# panda-2.net
KiCad netlist of a schematic drawn in EAGLE
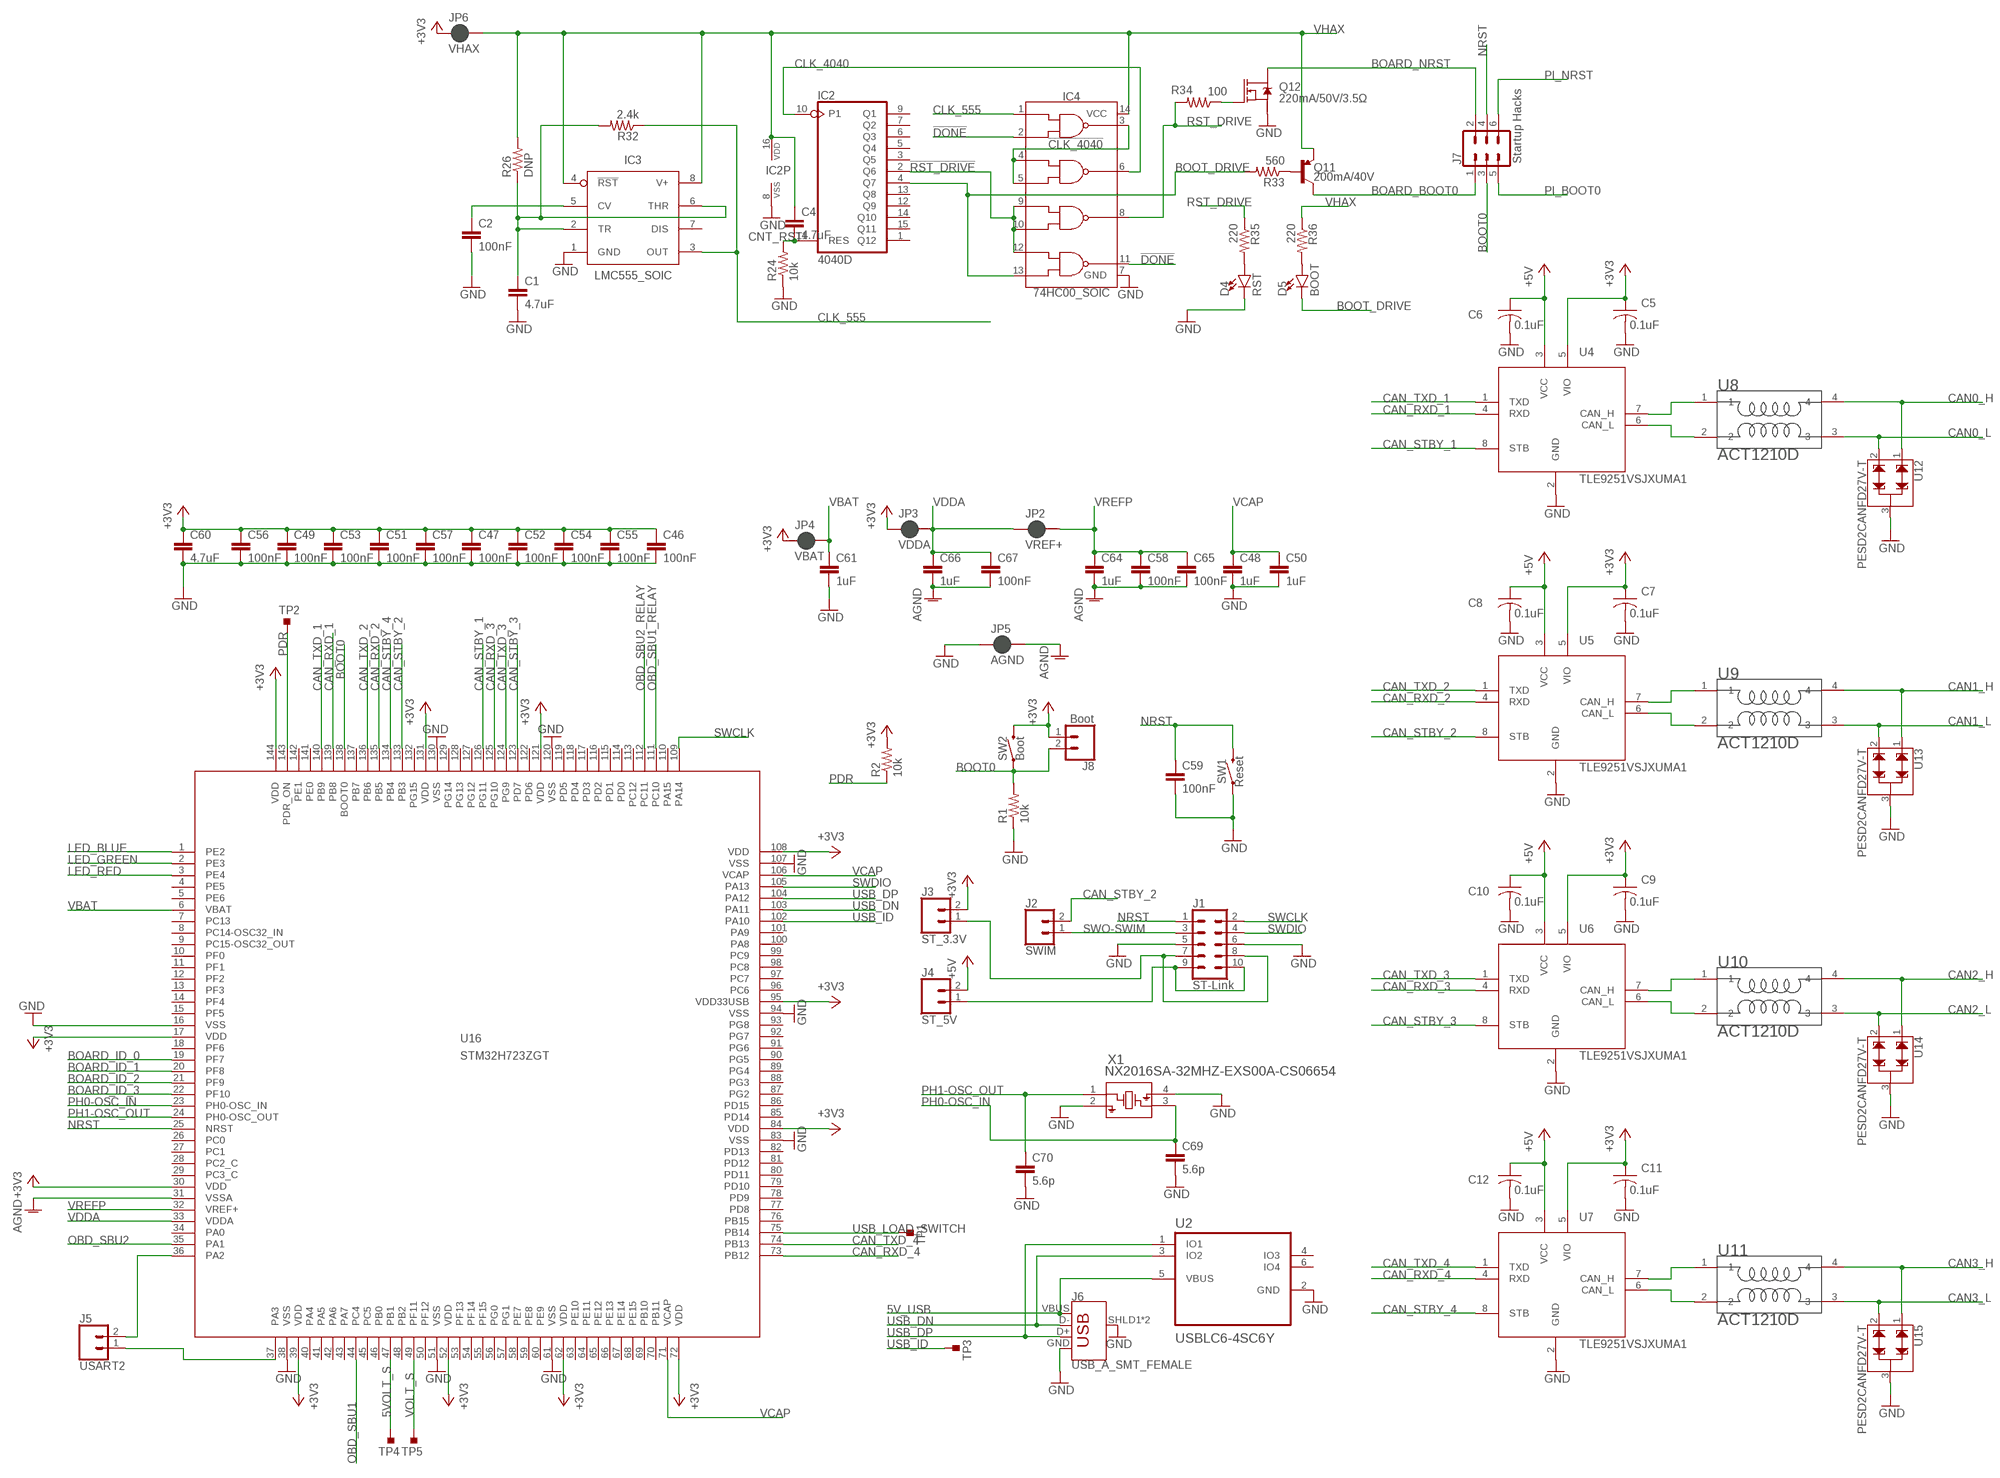
[diagram p0: schematic, sheet 1, part 1 of 2]
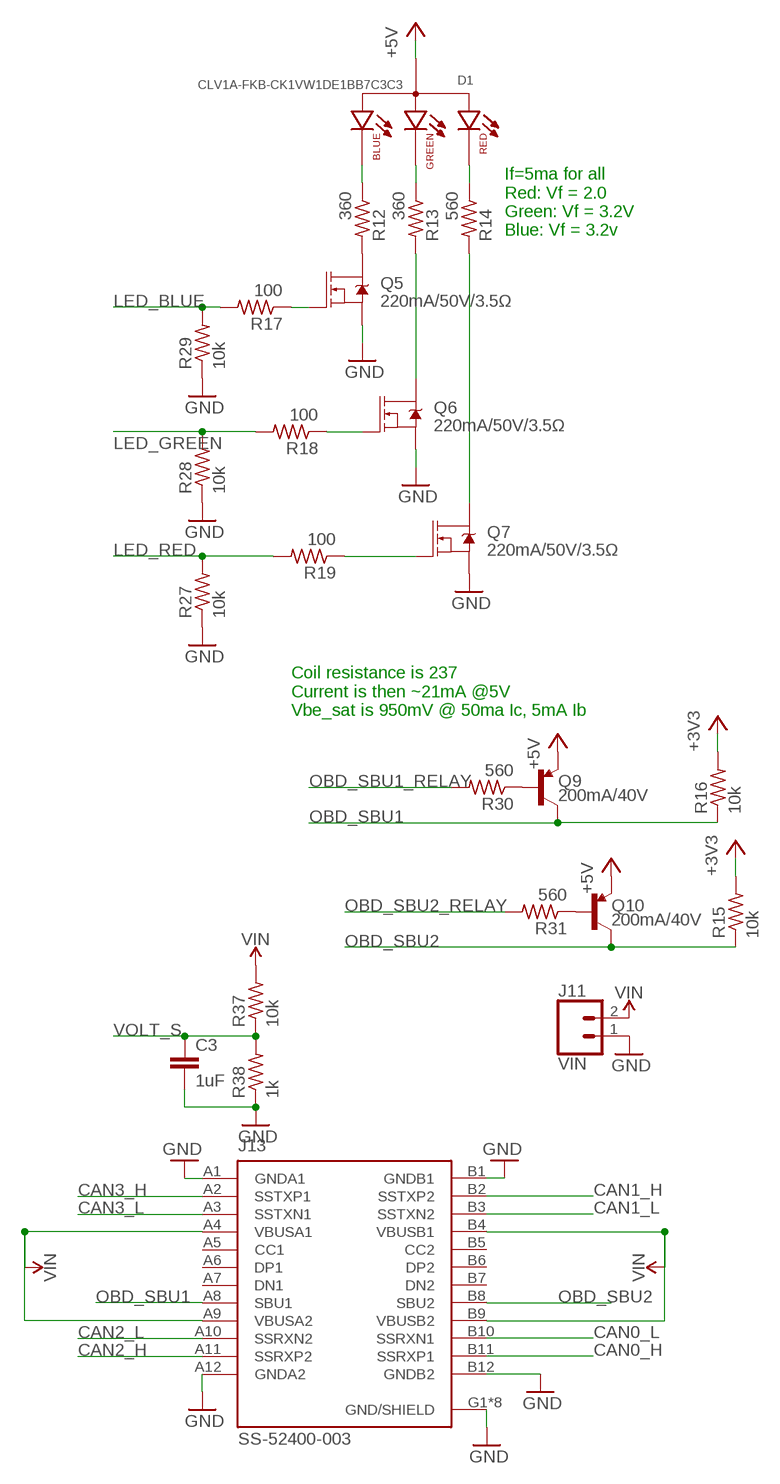
[diagram p1: schematic, sheet 1, part 2 of 2]
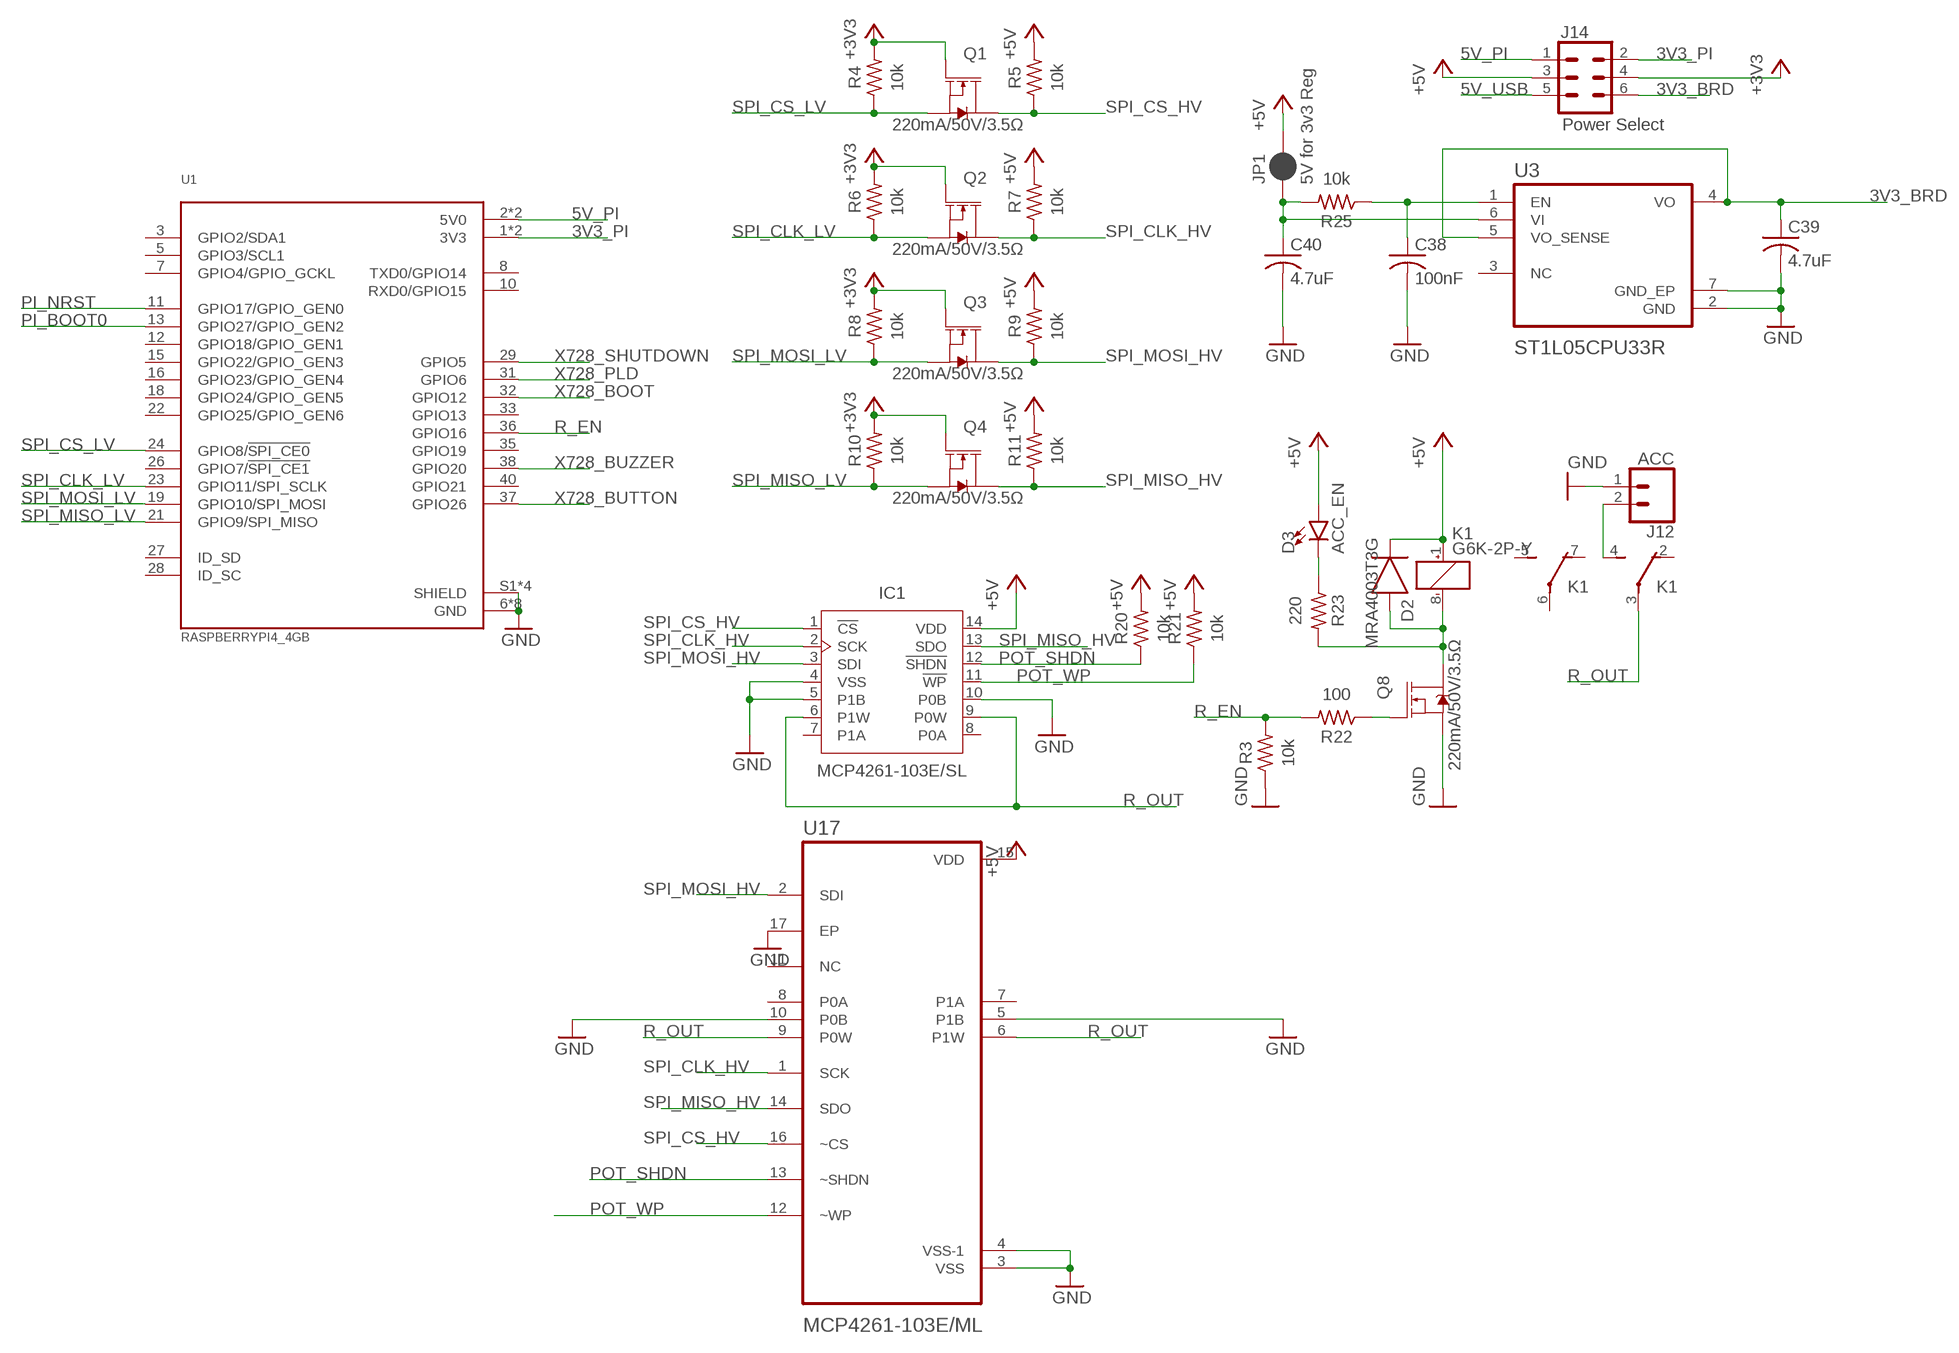
[diagram p2: schematic, sheet 2]

(export (version "E")
  (design (tool "Eeschema 10.0.6"))
  (components
    (comp (ref "C38")
      (value "100nF")
      (footprint "eagle-import:CAPC1005X60")
      (libsource (lib "eagle-import") (part "C-USCHIP-0402(1005-METRIC)_"))
    )
    (comp (ref "C39")
      (value "4.7uF")
      (footprint "eagle-import:CAPC1608X85")
      (libsource (lib "eagle-import") (part "C-USCHIP-0603(1608-METRIC)_"))
    )
    (comp (ref "C40")
      (value "4.7uF")
      (footprint "eagle-import:CAPC1608X85")
      (libsource (lib "eagle-import") (part "C-USCHIP-0603(1608-METRIC)_"))
    )
    (comp (ref "D2")
      (value "MRA4003T3G")
      (footprint "eagle-import:DIOM5226X290N")
      (fields (field (name "MANUFACTURER") "ON Semiconductor "))
      (libsource (lib "eagle-import") (part "DIODE__SMAMRA4003T3G"))
    )
    (comp (ref "D3")
      (value "ACC_EN")
      (footprint "eagle-import:LED-0603")
      (libsource (lib "eagle-import") (part "LED-RED0603"))
    )
    (comp (ref "IC1")
      (value "MCP4261-103E/SL")
      (footprint "eagle-import:SOIC127P600X175-14N")
      (fields (field (name "MANUFACTURER") "Microchip Technology"))
      (libsource (lib "eagle-import") (part "MCP42SOIC-1461-103E/SL"))
    )
    (comp (ref "J12")
      (value "ACC")
      (footprint "eagle-import:SCREWTERMINAL-5MM-2")
      (libsource (lib "eagle-import") (part "CONN_025MM"))
    )
    (comp (ref "J14")
      (value "Power Select")
      (footprint "eagle-import:2X3")
      (libsource (lib "eagle-import") (part "CONN_03X2FEMALE"))
    )
    (comp (ref "JP1")
      (value "5V for 3v3 Reg")
      (footprint "eagle-import:SMT-JUMPER_2_NC_PASTE_SILK")
      (libsource (lib "eagle-import") (part "JUMPER-SMT_2_NC_PASTE_SILK"))
    )
    (comp (ref "K1")
      (value "G6K-2P-Y")
      (footprint "eagle-import:G6K-2P-Y")
      (fields (field (name "MF") "OMRON COMPONENTS USA") (field (name "MPN") "G6K-2P-Y DC12"))
      (libsource (lib "eagle-import") (part "G6K-2P-Y"))
    )
    (comp (ref "Q1")
      (value "220mA/50V/3.5Ω")
      (footprint "eagle-import:SOT23-3")
      (libsource (lib "eagle-import") (part "MOSFET-NCH-BSS138"))
    )
    (comp (ref "Q2")
      (value "220mA/50V/3.5Ω")
      (footprint "eagle-import:SOT23-3")
      (libsource (lib "eagle-import") (part "MOSFET-NCH-BSS138"))
    )
    (comp (ref "Q3")
      (value "220mA/50V/3.5Ω")
      (footprint "eagle-import:SOT23-3")
      (libsource (lib "eagle-import") (part "MOSFET-NCH-BSS138"))
    )
    (comp (ref "Q4")
      (value "220mA/50V/3.5Ω")
      (footprint "eagle-import:SOT23-3")
      (libsource (lib "eagle-import") (part "MOSFET-NCH-BSS138"))
    )
    (comp (ref "Q8")
      (value "220mA/50V/3.5Ω")
      (footprint "eagle-import:SOT23-3")
      (libsource (lib "eagle-import") (part "MOSFET-NCH-BSS138"))
    )
    (comp (ref "R3")
      (value "10k")
      (footprint "eagle-import:RESC1005X40")
      (libsource (lib "eagle-import") (part "R-USCHIP-0402(1005-METRIC)_"))
    )
    (comp (ref "R4")
      (value "10k")
      (footprint "eagle-import:RESC1005X40")
      (libsource (lib "eagle-import") (part "R-USCHIP-0402(1005-METRIC)_"))
    )
    (comp (ref "R5")
      (value "10k")
      (footprint "eagle-import:RESC1005X40")
      (libsource (lib "eagle-import") (part "R-USCHIP-0402(1005-METRIC)_"))
    )
    (comp (ref "R6")
      (value "10k")
      (footprint "eagle-import:RESC1005X40")
      (libsource (lib "eagle-import") (part "R-USCHIP-0402(1005-METRIC)_"))
    )
    (comp (ref "R7")
      (value "10k")
      (footprint "eagle-import:RESC1005X40")
      (libsource (lib "eagle-import") (part "R-USCHIP-0402(1005-METRIC)_"))
    )
    (comp (ref "R8")
      (value "10k")
      (footprint "eagle-import:RESC1005X40")
      (libsource (lib "eagle-import") (part "R-USCHIP-0402(1005-METRIC)_"))
    )
    (comp (ref "R9")
      (value "10k")
      (footprint "eagle-import:RESC1005X40")
      (libsource (lib "eagle-import") (part "R-USCHIP-0402(1005-METRIC)_"))
    )
    (comp (ref "R10")
      (value "10k")
      (footprint "eagle-import:RESC1005X40")
      (libsource (lib "eagle-import") (part "R-USCHIP-0402(1005-METRIC)_"))
    )
    (comp (ref "R11")
      (value "10k")
      (footprint "eagle-import:RESC1005X40")
      (libsource (lib "eagle-import") (part "R-USCHIP-0402(1005-METRIC)_"))
    )
    (comp (ref "R20")
      (value "10k")
      (footprint "eagle-import:RESC1005X40")
      (libsource (lib "eagle-import") (part "R-USCHIP-0402(1005-METRIC)_"))
    )
    (comp (ref "R21")
      (value "10k")
      (footprint "eagle-import:RESC1005X40")
      (libsource (lib "eagle-import") (part "R-USCHIP-0402(1005-METRIC)_"))
    )
    (comp (ref "R22")
      (value "100")
      (footprint "eagle-import:RESC1005X40")
      (libsource (lib "eagle-import") (part "R-USCHIP-0402(1005-METRIC)_"))
    )
    (comp (ref "R23")
      (value "220")
      (footprint "eagle-import:RESC1005X40")
      (libsource (lib "eagle-import") (part "R-USCHIP-0402(1005-METRIC)_"))
    )
    (comp (ref "R25")
      (value "10k")
      (footprint "eagle-import:RESC1005X40")
      (libsource (lib "eagle-import") (part "R-USCHIP-0402(1005-METRIC)_"))
    )
    (comp (ref "U1")
      (value "RASPBERRYPI4_4GB")
      (footprint "eagle-import:MODULE_RASPBERRYPI4_4GB")
      (fields (field (name "MF") "Raspberry Pi") (field (name "MP") "RASPBERRY PI 4B/4GB"))
      (libsource (lib "eagle-import") (part "RASPBERRYPI4_4GB"))
    )
    (comp (ref "U3")
      (value "ST1L05CPU33R")
      (footprint "eagle-import:SON95P300X300X100-7N")
      (fields (field (name "MF") "STMicroelectronics"))
      (libsource (lib "eagle-import") (part "ST1L05CPU33R"))
    )
    (comp (ref "U17")
      (value "MCP4261-103E/ML")
      (footprint "eagle-import:QFN65P400X400X100-17N")
      (fields (field (name "MF") "Microchip"))
      (libsource (lib "eagle-import") (part "MCP4261-103E/ML"))
    )
    (comp (ref "C1")
      (value "4.7uF")
      (footprint "eagle-import:C0603")
      (libsource (lib "eagle-import") (part "C-EUC0603"))
    )
    (comp (ref "C2")
      (value "100nF")
      (footprint "eagle-import:C0402")
      (libsource (lib "eagle-import") (part "C-EUC0402"))
    )
    (comp (ref "C3")
      (value "1uF")
      (footprint "eagle-import:C0402")
      (libsource (lib "eagle-import") (part "C-EUC0402"))
    )
    (comp (ref "C4")
      (value "4.7uF")
      (footprint "eagle-import:C0603")
      (libsource (lib "eagle-import") (part "C-EUC0603"))
    )
    (comp (ref "C5")
      (value "0.1uF")
      (footprint "eagle-import:C0402")
      (libsource (lib "eagle-import") (part "C-USC0402"))
    )
    (comp (ref "C6")
      (value "0.1uF")
      (footprint "eagle-import:C0402")
      (libsource (lib "eagle-import") (part "C-USC0402"))
    )
    (comp (ref "C7")
      (value "0.1uF")
      (footprint "eagle-import:C0402")
      (libsource (lib "eagle-import") (part "C-USC0402"))
    )
    (comp (ref "C8")
      (value "0.1uF")
      (footprint "eagle-import:C0402")
      (libsource (lib "eagle-import") (part "C-USC0402"))
    )
    (comp (ref "C9")
      (value "0.1uF")
      (footprint "eagle-import:C0402")
      (libsource (lib "eagle-import") (part "C-USC0402"))
    )
    (comp (ref "C10")
      (value "0.1uF")
      (footprint "eagle-import:C0402")
      (libsource (lib "eagle-import") (part "C-USC0402"))
    )
    (comp (ref "C11")
      (value "0.1uF")
      (footprint "eagle-import:C0402")
      (libsource (lib "eagle-import") (part "C-USC0402"))
    )
    (comp (ref "C12")
      (value "0.1uF")
      (footprint "eagle-import:C0402")
      (libsource (lib "eagle-import") (part "C-USC0402"))
    )
    (comp (ref "C46")
      (value "100nF")
      (footprint "eagle-import:C0402")
      (libsource (lib "eagle-import") (part "C-EUC0402"))
    )
    (comp (ref "C47")
      (value "100nF")
      (footprint "eagle-import:C0402")
      (libsource (lib "eagle-import") (part "C-EUC0402"))
    )
    (comp (ref "C48")
      (value "1uF")
      (footprint "eagle-import:C0402")
      (libsource (lib "eagle-import") (part "C-EUC0402"))
    )
    (comp (ref "C49")
      (value "100nF")
      (footprint "eagle-import:C0402")
      (libsource (lib "eagle-import") (part "C-EUC0402"))
    )
    (comp (ref "C50")
      (value "1uF")
      (footprint "eagle-import:C0402")
      (libsource (lib "eagle-import") (part "C-EUC0402"))
    )
    (comp (ref "C51")
      (value "100nF")
      (footprint "eagle-import:C0402")
      (libsource (lib "eagle-import") (part "C-EUC0402"))
    )
    (comp (ref "C52")
      (value "100nF")
      (footprint "eagle-import:C0402")
      (libsource (lib "eagle-import") (part "C-EUC0402"))
    )
    (comp (ref "C53")
      (value "100nF")
      (footprint "eagle-import:C0402")
      (libsource (lib "eagle-import") (part "C-EUC0402"))
    )
    (comp (ref "C54")
      (value "100nF")
      (footprint "eagle-import:C0402")
      (libsource (lib "eagle-import") (part "C-EUC0402"))
    )
    (comp (ref "C55")
      (value "100nF")
      (footprint "eagle-import:C0402")
      (libsource (lib "eagle-import") (part "C-EUC0402"))
    )
    (comp (ref "C56")
      (value "100nF")
      (footprint "eagle-import:C0402")
      (libsource (lib "eagle-import") (part "C-EUC0402"))
    )
    (comp (ref "C57")
      (value "100nF")
      (footprint "eagle-import:C0402")
      (libsource (lib "eagle-import") (part "C-EUC0402"))
    )
    (comp (ref "C58")
      (value "100nF")
      (footprint "eagle-import:C0402")
      (libsource (lib "eagle-import") (part "C-EUC0402"))
    )
    (comp (ref "C59")
      (value "100nF")
      (footprint "eagle-import:C0402")
      (libsource (lib "eagle-import") (part "C-EUC0402"))
    )
    (comp (ref "C60")
      (value "4.7uF")
      (footprint "eagle-import:C0603")
      (libsource (lib "eagle-import") (part "C-EUC0603"))
    )
    (comp (ref "C61")
      (value "1uF")
      (footprint "eagle-import:C0402")
      (libsource (lib "eagle-import") (part "C-EUC0402"))
    )
    (comp (ref "C64")
      (value "1uF")
      (footprint "eagle-import:C0402")
      (libsource (lib "eagle-import") (part "C-EUC0402"))
    )
    (comp (ref "C65")
      (value "100nF")
      (footprint "eagle-import:C0402")
      (libsource (lib "eagle-import") (part "C-EUC0402"))
    )
    (comp (ref "C66")
      (value "1uF")
      (footprint "eagle-import:C0402")
      (libsource (lib "eagle-import") (part "C-EUC0402"))
    )
    (comp (ref "C67")
      (value "100nF")
      (footprint "eagle-import:C0402")
      (libsource (lib "eagle-import") (part "C-EUC0402"))
    )
    (comp (ref "C69")
      (value "5.6p")
      (footprint "eagle-import:C0402")
      (libsource (lib "eagle-import") (part "C-EUC0402"))
    )
    (comp (ref "C70")
      (value "5.6p")
      (footprint "eagle-import:C0402")
      (libsource (lib "eagle-import") (part "C-EUC0402"))
    )
    (comp (ref "D1")
      (value "CLV1A-FKB-CK1VW1DE1BB7C3C3")
      (footprint "eagle-import:LED_CLV1A-FKB-CK1VW1DE1BB7C3C3")
      (fields (field (name "MF") "Cree Inc."))
      (libsource (lib "eagle-import") (part "CLV1A-FKB-CK1VW1DE1BB7C3C3"))
    )
    (comp (ref "D4")
      (value "RST")
      (footprint "eagle-import:LED-0603")
      (libsource (lib "eagle-import") (part "LED-RED0603"))
    )
    (comp (ref "D5")
      (value "BOOT")
      (footprint "eagle-import:LED-0603")
      (libsource (lib "eagle-import") (part "LED-RED0603"))
    )
    (comp (ref "IC2")
      (value "4040D")
      (footprint "eagle-import:SO16")
      (libsource (lib "eagle-import") (part "4040D"))
    )
    (comp (ref "IC3")
      (value "LMC555_SOIC")
      (footprint "eagle-import:SOIC127P599X175-8N")
      (fields (field (name "MANUFACTURER") "Texas Instruments ") (field (name "MPN") "LMC555CM/NOPB "))
      (libsource (lib "eagle-import") (part "555_SOICLMC"))
    )
    (comp (ref "IC4")
      (value "74HC00_SOIC")
      (footprint "eagle-import:SOIC127P600X175-14N")
      (fields (field (name "MANUFACTURER") "Generic"))
      (libsource (lib "eagle-import") (part "74HC00_SOIC"))
    )
    (comp (ref "J1")
      (value "ST-Link")
      (footprint "eagle-import:2X5-SHROUDED-NS")
      (libsource (lib "eagle-import") (part "CONN_05X2SHD-NS"))
    )
    (comp (ref "J2")
      (value "SWIM")
      (footprint "eagle-import:1X02")
      (libsource (lib "eagle-import") (part "CONN_02"))
    )
    (comp (ref "J3")
      (value "ST_3.3V")
      (footprint "eagle-import:1X02")
      (libsource (lib "eagle-import") (part "CONN_02"))
    )
    (comp (ref "J4")
      (value "ST_5V")
      (footprint "eagle-import:1X02")
      (libsource (lib "eagle-import") (part "CONN_02"))
    )
    (comp (ref "J5")
      (value "USART2")
      (footprint "eagle-import:1X02")
      (libsource (lib "eagle-import") (part "CONN_02"))
    )
    (comp (ref "J6")
      (value "USB_A_SMT_FEMALE")
      (footprint "eagle-import:USB-A-S-SILK-FEMALE")
      (libsource (lib "eagle-import") (part "USB_A_SMT_FEMALE"))
    )
    (comp (ref "J7")
      (value "Startup Hacks")
      (footprint "eagle-import:2X3")
      (libsource (lib "eagle-import") (part "CONN_03X2FEMALE"))
    )
    (comp (ref "J8")
      (value "Boot")
      (footprint "eagle-import:1X02")
      (libsource (lib "eagle-import") (part "CONN_02"))
    )
    (comp (ref "J11")
      (value "VIN")
      (footprint "eagle-import:1X02")
      (libsource (lib "eagle-import") (part "CONN_02"))
    )
    (comp (ref "J13")
      (value "SS-52400-003")
      (footprint "eagle-import:BELFUSE_SS-52400-003")
      (fields (field (name "MF") "Stewart Connector"))
      (libsource (lib "eagle-import") (part "SS-52400-003"))
    )
    (comp (ref "JP2")
      (value "VREF+")
      (footprint "eagle-import:SMT-JUMPER_2_NC_PASTE_SILK")
      (libsource (lib "eagle-import") (part "JUMPER-SMT_2_NC_PASTE_SILK"))
    )
    (comp (ref "JP3")
      (value "VDDA")
      (footprint "eagle-import:SMT-JUMPER_2_NC_PASTE_SILK")
      (libsource (lib "eagle-import") (part "JUMPER-SMT_2_NC_PASTE_SILK"))
    )
    (comp (ref "JP4")
      (value "VBAT")
      (footprint "eagle-import:SMT-JUMPER_2_NC_PASTE_SILK")
      (libsource (lib "eagle-import") (part "JUMPER-SMT_2_NC_PASTE_SILK"))
    )
    (comp (ref "JP5")
      (value "AGND")
      (footprint "eagle-import:SMT-JUMPER_2_NC_PASTE_SILK")
      (libsource (lib "eagle-import") (part "JUMPER-SMT_2_NC_PASTE_SILK"))
    )
    (comp (ref "JP6")
      (value "VHAX")
      (footprint "eagle-import:SMT-JUMPER_2_NC_PASTE_SILK")
      (libsource (lib "eagle-import") (part "JUMPER-SMT_2_NC_PASTE_SILK"))
    )
    (comp (ref "Q5")
      (value "220mA/50V/3.5Ω")
      (footprint "eagle-import:SOT23-3")
      (libsource (lib "eagle-import") (part "MOSFET-NCH-BSS138"))
    )
    (comp (ref "Q6")
      (value "220mA/50V/3.5Ω")
      (footprint "eagle-import:SOT23-3")
      (libsource (lib "eagle-import") (part "MOSFET-NCH-BSS138"))
    )
    (comp (ref "Q7")
      (value "220mA/50V/3.5Ω")
      (footprint "eagle-import:SOT23-3")
      (libsource (lib "eagle-import") (part "MOSFET-NCH-BSS138"))
    )
    (comp (ref "Q9")
      (value "200mA/40V")
      (footprint "eagle-import:SOT23-3")
      (libsource (lib "eagle-import") (part "TRANS_PNP-PMBT3906|MMBT3906L"))
    )
    (comp (ref "Q10")
      (value "200mA/40V")
      (footprint "eagle-import:SOT23-3")
      (libsource (lib "eagle-import") (part "TRANS_PNP-PMBT3906|MMBT3906L"))
    )
    (comp (ref "Q11")
      (value "200mA/40V")
      (footprint "eagle-import:SOT23-3")
      (libsource (lib "eagle-import") (part "TRANS_PNP-PMBT3906|MMBT3906L"))
    )
    (comp (ref "Q12")
      (value "220mA/50V/3.5Ω")
      (footprint "eagle-import:SOT23-3")
      (libsource (lib "eagle-import") (part "MOSFET-NCH-BSS138"))
    )
    (comp (ref "R1")
      (value "10k")
      (footprint "eagle-import:R0402")
      (libsource (lib "eagle-import") (part "R-US_R0402"))
    )
    (comp (ref "R2")
      (value "10k")
      (footprint "eagle-import:R0402")
      (libsource (lib "eagle-import") (part "R-US_R0402"))
    )
    (comp (ref "R12")
      (value "360")
      (footprint "eagle-import:R0402")
      (libsource (lib "eagle-import") (part "R-US_R0402"))
    )
    (comp (ref "R13")
      (value "360")
      (footprint "eagle-import:R0402")
      (libsource (lib "eagle-import") (part "R-US_R0402"))
    )
    (comp (ref "R14")
      (value "560")
      (footprint "eagle-import:R0402")
      (libsource (lib "eagle-import") (part "R-US_R0402"))
    )
    (comp (ref "R15")
      (value "10k")
      (footprint "eagle-import:R0402")
      (libsource (lib "eagle-import") (part "R-US_R0402"))
    )
    (comp (ref "R16")
      (value "10k")
      (footprint "eagle-import:R0402")
      (libsource (lib "eagle-import") (part "R-US_R0402"))
    )
    (comp (ref "R17")
      (value "100")
      (footprint "eagle-import:R0402")
      (libsource (lib "eagle-import") (part "R-US_R0402"))
    )
    (comp (ref "R18")
      (value "100")
      (footprint "eagle-import:R0402")
      (libsource (lib "eagle-import") (part "R-US_R0402"))
    )
    (comp (ref "R19")
      (value "100")
      (footprint "eagle-import:R0402")
      (libsource (lib "eagle-import") (part "R-US_R0402"))
    )
    (comp (ref "R24")
      (value "10k")
      (footprint "eagle-import:R0402")
      (libsource (lib "eagle-import") (part "R-US_R0402"))
    )
    (comp (ref "R26")
      (value "DNP")
      (footprint "eagle-import:R0402")
      (libsource (lib "eagle-import") (part "R-US_R0402"))
    )
    (comp (ref "R27")
      (value "10k")
      (footprint "eagle-import:R0402")
      (libsource (lib "eagle-import") (part "R-US_R0402"))
    )
    (comp (ref "R28")
      (value "10k")
      (footprint "eagle-import:R0402")
      (libsource (lib "eagle-import") (part "R-US_R0402"))
    )
    (comp (ref "R29")
      (value "10k")
      (footprint "eagle-import:R0402")
      (libsource (lib "eagle-import") (part "R-US_R0402"))
    )
    (comp (ref "R30")
      (value "560")
      (footprint "eagle-import:R0402")
      (libsource (lib "eagle-import") (part "R-US_R0402"))
    )
    (comp (ref "R31")
      (value "560")
      (footprint "eagle-import:R0402")
      (libsource (lib "eagle-import") (part "R-US_R0402"))
    )
    (comp (ref "R32")
      (value "2.4k")
      (footprint "eagle-import:R0402")
      (libsource (lib "eagle-import") (part "R-US_R0402"))
    )
    (comp (ref "R33")
      (value "560")
      (footprint "eagle-import:R0402")
      (libsource (lib "eagle-import") (part "R-US_R0402"))
    )
    (comp (ref "R34")
      (value "100")
      (footprint "eagle-import:R0402")
      (libsource (lib "eagle-import") (part "R-US_R0402"))
    )
    (comp (ref "R35")
      (value "220")
      (footprint "eagle-import:R0402")
      (libsource (lib "eagle-import") (part "R-US_R0402"))
    )
    (comp (ref "R36")
      (value "220")
      (footprint "eagle-import:R0402")
      (libsource (lib "eagle-import") (part "R-US_R0402"))
    )
    (comp (ref "R37")
      (value "10k")
      (footprint "eagle-import:R0402")
      (libsource (lib "eagle-import") (part "R-US_R0402"))
    )
    (comp (ref "R38")
      (value "1k")
      (footprint "eagle-import:R0402")
      (libsource (lib "eagle-import") (part "R-US_R0402"))
    )
    (comp (ref "SW1")
      (value "Reset")
      (footprint "eagle-import:TACTILE_SWITCH_PTH_6.0MM")
      (libsource (lib "eagle-import") (part "MOMENTARY-SWITCH-SPST-PTH-6.0MM"))
    )
    (comp (ref "SW2")
      (value "Boot")
      (footprint "eagle-import:TACTILE_SWITCH_PTH_6.0MM")
      (libsource (lib "eagle-import") (part "MOMENTARY-SWITCH-SPST-PTH-6.0MM"))
    )
    (comp (ref "TP1")
      (value "USB_LOAD_SWITCH")
      (footprint "eagle-import:TESTPOINT_SMD-10SN")
      (libsource (lib "eagle-import") (part "TESTPOINT_TPS-SMD-10SN"))
    )
    (comp (ref "TP2")
      (value "PDR_ON")
      (footprint "eagle-import:TESTPOINT_SMD-10SN")
      (libsource (lib "eagle-import") (part "TESTPOINT_TPS-SMD-10SN"))
    )
    (comp (ref "TP3")
      (value "USB_ID")
      (footprint "eagle-import:TESTPOINT_SMD-10SN")
      (libsource (lib "eagle-import") (part "TESTPOINT_TPS-SMD-10SN"))
    )
    (comp (ref "TP4")
      (value "5VOUT_S")
      (footprint "eagle-import:TESTPOINT_SMD-10SN")
      (libsource (lib "eagle-import") (part "TESTPOINT_TPS-SMD-10SN"))
    )
    (comp (ref "TP5")
      (value "VOLT_S")
      (footprint "eagle-import:TESTPOINT_SMD-10SN")
      (libsource (lib "eagle-import") (part "TESTPOINT_TPS-SMD-10SN"))
    )
    (comp (ref "U2")
      (value "USBLC6-4SC6Y")
      (footprint "eagle-import:SOT95P280X145-6N")
      (fields (field (name "MF") "STMicroelectronics"))
      (libsource (lib "eagle-import") (part "USBLC6-4SC6Y"))
    )
    (comp (ref "U4")
      (value "TLE9251VSJXUMA1")
      (footprint "eagle-import:SOIC8")
      (libsource (lib "eagle-import") (part "TLE9251VSJXUMA1"))
    )
    (comp (ref "U5")
      (value "TLE9251VSJXUMA1")
      (footprint "eagle-import:SOIC8")
      (libsource (lib "eagle-import") (part "TLE9251VSJXUMA1"))
    )
    (comp (ref "U6")
      (value "TLE9251VSJXUMA1")
      (footprint "eagle-import:SOIC8")
      (libsource (lib "eagle-import") (part "TLE9251VSJXUMA1"))
    )
    (comp (ref "U7")
      (value "TLE9251VSJXUMA1")
      (footprint "eagle-import:SOIC8")
      (libsource (lib "eagle-import") (part "TLE9251VSJXUMA1"))
    )
    (comp (ref "U8")
      (value "ACT1210D")
      (footprint "eagle-import:ACT1210-101-2P-TL")
      (libsource (lib "eagle-import") (part "ACT1210D"))
    )
    (comp (ref "U9")
      (value "ACT1210D")
      (footprint "eagle-import:ACT1210-101-2P-TL")
      (libsource (lib "eagle-import") (part "ACT1210D"))
    )
    (comp (ref "U10")
      (value "ACT1210D")
      (footprint "eagle-import:ACT1210-101-2P-TL")
      (libsource (lib "eagle-import") (part "ACT1210D"))
    )
    (comp (ref "U11")
      (value "ACT1210D")
      (footprint "eagle-import:ACT1210-101-2P-TL")
      (libsource (lib "eagle-import") (part "ACT1210D"))
    )
    (comp (ref "U12")
      (value "PESD2CANFD27V-T")
      (footprint "eagle-import:DBZ_R-PDSO-G3")
      (libsource (lib "eagle-import") (part "PESD2CANFD27V-T"))
    )
    (comp (ref "U13")
      (value "PESD2CANFD27V-T")
      (footprint "eagle-import:DBZ_R-PDSO-G3")
      (libsource (lib "eagle-import") (part "PESD2CANFD27V-T"))
    )
    (comp (ref "U14")
      (value "PESD2CANFD27V-T")
      (footprint "eagle-import:DBZ_R-PDSO-G3")
      (libsource (lib "eagle-import") (part "PESD2CANFD27V-T"))
    )
    (comp (ref "U15")
      (value "PESD2CANFD27V-T")
      (footprint "eagle-import:DBZ_R-PDSO-G3")
      (libsource (lib "eagle-import") (part "PESD2CANFD27V-T"))
    )
    (comp (ref "U16")
      (value "STM32H723ZGT")
      (footprint "eagle-import:LQFP-144")
      (libsource (lib "eagle-import") (part "STM32H723ZGT"))
    )
    (comp (ref "X1")
      (value "NX2016SA-32MHZ-EXS00A-CS06654")
      (footprint "eagle-import:NX2016SA_NDK")
      (fields (field (name "COPYRIGHT") "Copyright (C) 2022 Ultra Librarian. All rights reserved."))
      (libsource (lib "eagle-import") (part "NX2016SA-32MHZ-EXS00A-CS06654"))
    )
  )
  (nets
    (net (code "1") (name "+3V3") (class "Default")
      (node (ref "C11") (pin "1") (pinfunction "1_1") (pintype "passive"))
      (node (ref "C46") (pin "1") (pinfunction "1_1") (pintype "passive"))
      (node (ref "C47") (pin "1") (pinfunction "1_1") (pintype "passive"))
      (node (ref "C49") (pin "1") (pinfunction "1_1") (pintype "passive"))
      (node (ref "C5") (pin "1") (pinfunction "1_1") (pintype "passive"))
      (node (ref "C51") (pin "1") (pinfunction "1_1") (pintype "passive"))
      (node (ref "C52") (pin "1") (pinfunction "1_1") (pintype "passive"))
      (node (ref "C53") (pin "1") (pinfunction "1_1") (pintype "passive"))
      (node (ref "C54") (pin "1") (pinfunction "1_1") (pintype "passive"))
      (node (ref "C55") (pin "1") (pinfunction "1_1") (pintype "passive"))
      (node (ref "C56") (pin "1") (pinfunction "1_1") (pintype "passive"))
      (node (ref "C57") (pin "1") (pinfunction "1_1") (pintype "passive"))
      (node (ref "C60") (pin "1") (pinfunction "1_1") (pintype "passive"))
      (node (ref "C7") (pin "1") (pinfunction "1_1") (pintype "passive"))
      (node (ref "C9") (pin "1") (pinfunction "1_1") (pintype "passive"))
      (node (ref "J14") (pin "4") (pinfunction "4_4") (pintype "bidirectional"))
      (node (ref "J3") (pin "2") (pinfunction "2_2") (pintype "passive"))
      (node (ref "J8") (pin "1") (pinfunction "1_1") (pintype "passive"))
      (node (ref "JP3") (pin "1") (pinfunction "1_1") (pintype "passive"))
      (node (ref "JP4") (pin "1") (pinfunction "1_1") (pintype "passive"))
      (node (ref "JP6") (pin "1") (pinfunction "1_1") (pintype "passive"))
      (node (ref "Q1") (pin "1") (pinfunction "G_1") (pintype "bidirectional"))
      (node (ref "Q2") (pin "1") (pinfunction "G_1") (pintype "bidirectional"))
      (node (ref "Q3") (pin "1") (pinfunction "G_1") (pintype "bidirectional"))
      (node (ref "Q4") (pin "1") (pinfunction "G_1") (pintype "bidirectional"))
      (node (ref "R10") (pin "2") (pinfunction "2_2") (pintype "passive"))
      (node (ref "R15") (pin "2") (pinfunction "2_2") (pintype "passive"))
      (node (ref "R16") (pin "2") (pinfunction "2_2") (pintype "passive"))
      (node (ref "R2") (pin "2") (pinfunction "2_2") (pintype "passive"))
      (node (ref "R4") (pin "2") (pinfunction "2_2") (pintype "passive"))
      (node (ref "R6") (pin "2") (pinfunction "2_2") (pintype "passive"))
      (node (ref "R8") (pin "2") (pinfunction "2_2") (pintype "passive"))
      (node (ref "SW2") (pin "3") (pinfunction "2_3") (pintype "passive"))
      (node (ref "U16") (pin "108") (pinfunction "VDD_108") (pintype "power_in"))
      (node (ref "U16") (pin "121") (pinfunction "VDD_121") (pintype "power_in"))
      (node (ref "U16") (pin "131") (pinfunction "VDD_131") (pintype "power_in"))
      (node (ref "U16") (pin "144") (pinfunction "VDD_144") (pintype "power_in"))
      (node (ref "U16") (pin "17") (pinfunction "VDD_17") (pintype "power_in"))
      (node (ref "U16") (pin "30") (pinfunction "VDD_30") (pintype "power_in"))
      (node (ref "U16") (pin "39") (pinfunction "VDD_39") (pintype "power_in"))
      (node (ref "U16") (pin "52") (pinfunction "VDD_52") (pintype "power_in"))
      (node (ref "U16") (pin "62") (pinfunction "VDD_62") (pintype "power_in"))
      (node (ref "U16") (pin "72") (pinfunction "VDD_72") (pintype "power_in"))
      (node (ref "U16") (pin "84") (pinfunction "VDD_84") (pintype "power_in"))
      (node (ref "U16") (pin "95") (pinfunction "VDD33USB_95") (pintype "power_in"))
      (node (ref "U4") (pin "5") (pinfunction "VIO_5") (pintype "bidirectional"))
      (node (ref "U5") (pin "5") (pinfunction "VIO_5") (pintype "bidirectional"))
      (node (ref "U6") (pin "5") (pinfunction "VIO_5") (pintype "bidirectional"))
      (node (ref "U7") (pin "5") (pinfunction "VIO_5") (pintype "bidirectional"))
    )
    (net (code "2") (name "+5V") (class "Default")
      (node (ref "C10") (pin "1") (pinfunction "1_1") (pintype "passive"))
      (node (ref "C12") (pin "1") (pinfunction "1_1") (pintype "passive"))
      (node (ref "C6") (pin "1") (pinfunction "1_1") (pintype "passive"))
      (node (ref "C8") (pin "1") (pinfunction "1_1") (pintype "passive"))
      (node (ref "D1") (pin "2") (pinfunction "A_2") (pintype "passive"))
      (node (ref "D2") (pin "1") (pinfunction "C_1") (pintype "passive"))
      (node (ref "D3") (pin "A") (pinfunction "A_A") (pintype "passive"))
      (node (ref "IC1") (pin "14") (pinfunction "VDD_14") (pintype "power_in"))
      (node (ref "J14") (pin "3") (pinfunction "3_3") (pintype "bidirectional"))
      (node (ref "J4") (pin "2") (pinfunction "2_2") (pintype "passive"))
      (node (ref "JP1") (pin "2") (pinfunction "2_2") (pintype "passive"))
      (node (ref "K1") (pin "1") (pinfunction "+_1") (pintype "passive"))
      (node (ref "Q10") (pin "2") (pinfunction "E_2") (pintype "passive"))
      (node (ref "Q9") (pin "2") (pinfunction "E_2") (pintype "passive"))
      (node (ref "R11") (pin "2") (pinfunction "2_2") (pintype "passive"))
      (node (ref "R20") (pin "2") (pinfunction "2_2") (pintype "passive"))
      (node (ref "R21") (pin "2") (pinfunction "2_2") (pintype "passive"))
      (node (ref "R5") (pin "2") (pinfunction "2_2") (pintype "passive"))
      (node (ref "R7") (pin "2") (pinfunction "2_2") (pintype "passive"))
      (node (ref "R9") (pin "2") (pinfunction "2_2") (pintype "passive"))
      (node (ref "U17") (pin "15") (pinfunction "VDD_15") (pintype "power_in"))
      (node (ref "U4") (pin "3") (pinfunction "VCC_3") (pintype "bidirectional"))
      (node (ref "U5") (pin "3") (pinfunction "VCC_3") (pintype "bidirectional"))
      (node (ref "U6") (pin "3") (pinfunction "VCC_3") (pintype "bidirectional"))
      (node (ref "U7") (pin "3") (pinfunction "VCC_3") (pintype "bidirectional"))
    )
    (net (code "3") (name "3V3_BRD") (class "Default")
      (node (ref "C39") (pin "1") (pinfunction "1_1") (pintype "passive"))
      (node (ref "J14") (pin "6") (pinfunction "6_6") (pintype "bidirectional"))
      (node (ref "U3") (pin "4") (pinfunction "VO_4") (pintype "output"))
      (node (ref "U3") (pin "5") (pinfunction "VO_SENSE_5") (pintype "input"))
    )
    (net (code "4") (name "3V3_PI") (class "Default")
      (node (ref "J14") (pin "2") (pinfunction "2_2") (pintype "bidirectional"))
      (node (ref "U1") (pin "1") (pinfunction "3V3_1") (pintype "power_in"))
      (node (ref "U1") (pin "17") (pinfunction "3V3_17") (pintype "power_in"))
    )
    (net (code "5") (name "5VOLT_S") (class "Default")
      (node (ref "TP4") (pin "TP") (pinfunction "TP_TP") (pintype "passive"))
      (node (ref "U16") (pin "47") (pinfunction "PB1_47") (pintype "bidirectional"))
    )
    (net (code "6") (name "5V_PI") (class "Default")
      (node (ref "J14") (pin "1") (pinfunction "1_1") (pintype "bidirectional"))
      (node (ref "U1") (pin "2") (pinfunction "5V0_2") (pintype "power_in"))
      (node (ref "U1") (pin "4") (pinfunction "5V0_4") (pintype "power_in"))
    )
    (net (code "7") (name "5V_USB") (class "Default")
      (node (ref "J14") (pin "5") (pinfunction "5_5") (pintype "bidirectional"))
      (node (ref "J6") (pin "VBUS") (pinfunction "VBUS_VBUS") (pintype "power_in"))
      (node (ref "U2") (pin "5") (pinfunction "VBUS_5") (pintype "bidirectional"))
    )
    (net (code "8") (name "AGND") (class "Default")
      (node (ref "C58") (pin "2") (pinfunction "2_2") (pintype "passive"))
      (node (ref "C64") (pin "2") (pinfunction "2_2") (pintype "passive"))
      (node (ref "C65") (pin "2") (pinfunction "2_2") (pintype "passive"))
      (node (ref "C66") (pin "2") (pinfunction "2_2") (pintype "passive"))
      (node (ref "C67") (pin "2") (pinfunction "2_2") (pintype "passive"))
      (node (ref "JP5") (pin "2") (pinfunction "2_2") (pintype "passive"))
      (node (ref "U16") (pin "31") (pinfunction "VSSA_31") (pintype "power_in"))
    )
    (net (code "9") (name "BOARD_BOOT0") (class "Default")
      (node (ref "J7") (pin "1") (pinfunction "1_1") (pintype "bidirectional"))
      (node (ref "Q11") (pin "3") (pinfunction "C_3") (pintype "passive"))
    )
    (net (code "10") (name "BOARD_ID_0") (class "Default")
      (node (ref "U16") (pin "19") (pinfunction "PF7_19") (pintype "bidirectional"))
    )
    (net (code "11") (name "BOARD_ID_1") (class "Default")
      (node (ref "U16") (pin "20") (pinfunction "PF8_20") (pintype "bidirectional"))
    )
    (net (code "12") (name "BOARD_ID_2") (class "Default")
      (node (ref "U16") (pin "21") (pinfunction "PF9_21") (pintype "bidirectional"))
    )
    (net (code "13") (name "BOARD_ID_3") (class "Default")
      (node (ref "U16") (pin "22") (pinfunction "PF10_22") (pintype "bidirectional"))
    )
    (net (code "14") (name "BOARD_NRST") (class "Default")
      (node (ref "J7") (pin "2") (pinfunction "2_2") (pintype "bidirectional"))
      (node (ref "Q12") (pin "3") (pinfunction "D_3") (pintype "bidirectional"))
    )
    (net (code "15") (name "BOOT0") (class "Default")
      (node (ref "J7") (pin "3") (pinfunction "3_3") (pintype "bidirectional"))
      (node (ref "J8") (pin "2") (pinfunction "2_2") (pintype "passive"))
      (node (ref "R1") (pin "2") (pinfunction "2_2") (pintype "passive"))
      (node (ref "SW2") (pin "1") (pinfunction "1_1") (pintype "passive"))
      (node (ref "U16") (pin "138") (pinfunction "BOOT0_138") (pintype "bidirectional"))
    )
    (net (code "16") (name "BOOT_DRIVE") (class "Default")
      (node (ref "D5") (pin "C") (pinfunction "C_C") (pintype "passive"))
      (node (ref "IC2") (pin "4") (pinfunction "Q7_4") (pintype "output"))
      (node (ref "IC4") (pin "13") (pinfunction "4B_13") (pintype "input"))
      (node (ref "R33") (pin "2") (pinfunction "2_2") (pintype "passive"))
    )
    (net (code "17") (name "CAN0_H") (class "Default")
      (node (ref "J13") (pin "B11") (pinfunction "SSRXP1_B11") (pintype "bidirectional"))
      (node (ref "U12") (pin "1") (pinfunction "1_1") (pintype "bidirectional"))
      (node (ref "U8") (pin "4") (pinfunction "4_4") (pintype "bidirectional"))
    )
    (net (code "18") (name "CAN0_L") (class "Default")
      (node (ref "J13") (pin "B10") (pinfunction "SSRXN1_B10") (pintype "bidirectional"))
      (node (ref "U12") (pin "2") (pinfunction "2_2") (pintype "bidirectional"))
      (node (ref "U8") (pin "3") (pinfunction "3_3") (pintype "bidirectional"))
    )
    (net (code "19") (name "CAN1_H") (class "Default")
      (node (ref "J13") (pin "B2") (pinfunction "SSTXP2_B2") (pintype "bidirectional"))
      (node (ref "U13") (pin "1") (pinfunction "1_1") (pintype "bidirectional"))
      (node (ref "U9") (pin "4") (pinfunction "4_4") (pintype "bidirectional"))
    )
    (net (code "20") (name "CAN1_L") (class "Default")
      (node (ref "J13") (pin "B3") (pinfunction "SSTXN2_B3") (pintype "bidirectional"))
      (node (ref "U13") (pin "2") (pinfunction "2_2") (pintype "bidirectional"))
      (node (ref "U9") (pin "3") (pinfunction "3_3") (pintype "bidirectional"))
    )
    (net (code "21") (name "CAN2_H") (class "Default")
      (node (ref "J13") (pin "A11") (pinfunction "SSRXP2_A11") (pintype "bidirectional"))
      (node (ref "U10") (pin "4") (pinfunction "4_4") (pintype "bidirectional"))
      (node (ref "U14") (pin "1") (pinfunction "1_1") (pintype "bidirectional"))
    )
    (net (code "22") (name "CAN2_L") (class "Default")
      (node (ref "J13") (pin "A10") (pinfunction "SSRXN2_A10") (pintype "bidirectional"))
      (node (ref "U10") (pin "3") (pinfunction "3_3") (pintype "bidirectional"))
      (node (ref "U14") (pin "2") (pinfunction "2_2") (pintype "bidirectional"))
    )
    (net (code "23") (name "CAN3_H") (class "Default")
      (node (ref "J13") (pin "A2") (pinfunction "SSTXP1_A2") (pintype "bidirectional"))
      (node (ref "U11") (pin "4") (pinfunction "4_4") (pintype "bidirectional"))
      (node (ref "U15") (pin "1") (pinfunction "1_1") (pintype "bidirectional"))
    )
    (net (code "24") (name "CAN3_L") (class "Default")
      (node (ref "J13") (pin "A3") (pinfunction "SSTXN1_A3") (pintype "bidirectional"))
      (node (ref "U11") (pin "3") (pinfunction "3_3") (pintype "bidirectional"))
      (node (ref "U15") (pin "2") (pinfunction "2_2") (pintype "bidirectional"))
    )
    (net (code "25") (name "CAN_RXD_1") (class "Default")
      (node (ref "U16") (pin "139") (pinfunction "PB8_139") (pintype "bidirectional"))
      (node (ref "U4") (pin "4") (pinfunction "RXD_4") (pintype "bidirectional"))
    )
    (net (code "26") (name "CAN_RXD_2") (class "Default")
      (node (ref "U16") (pin "135") (pinfunction "PB5_135") (pintype "bidirectional"))
      (node (ref "U5") (pin "4") (pinfunction "RXD_4") (pintype "bidirectional"))
    )
    (net (code "27") (name "CAN_RXD_3") (class "Default")
      (node (ref "U16") (pin "125") (pinfunction "PG10_125") (pintype "bidirectional"))
      (node (ref "U6") (pin "4") (pinfunction "RXD_4") (pintype "bidirectional"))
    )
    (net (code "28") (name "CAN_RXD_4") (class "Default")
      (node (ref "U16") (pin "73") (pinfunction "PB12_73") (pintype "bidirectional"))
      (node (ref "U7") (pin "4") (pinfunction "RXD_4") (pintype "bidirectional"))
    )
    (net (code "29") (name "CAN_STBY_1") (class "Default")
      (node (ref "U16") (pin "126") (pinfunction "PG11_126") (pintype "bidirectional"))
      (node (ref "U4") (pin "8") (pinfunction "STB_8") (pintype "bidirectional"))
    )
    (net (code "30") (name "CAN_STBY_2") (class "Default")
      (node (ref "J2") (pin "2") (pinfunction "2_2") (pintype "passive"))
      (node (ref "U16") (pin "133") (pinfunction "PB3_133") (pintype "bidirectional"))
      (node (ref "U5") (pin "8") (pinfunction "STB_8") (pintype "bidirectional"))
    )
    (net (code "31") (name "CAN_STBY_3") (class "Default")
      (node (ref "U16") (pin "123") (pinfunction "PD7_123") (pintype "bidirectional"))
      (node (ref "U6") (pin "8") (pinfunction "STB_8") (pintype "bidirectional"))
    )
    (net (code "32") (name "CAN_STBY_4") (class "Default")
      (node (ref "U16") (pin "134") (pinfunction "PB4_134") (pintype "bidirectional"))
      (node (ref "U7") (pin "8") (pinfunction "STB_8") (pintype "bidirectional"))
    )
    (net (code "33") (name "CAN_TXD_1") (class "Default")
      (node (ref "U16") (pin "140") (pinfunction "PB9_140") (pintype "bidirectional"))
      (node (ref "U4") (pin "1") (pinfunction "TXD_1") (pintype "bidirectional"))
    )
    (net (code "34") (name "CAN_TXD_2") (class "Default")
      (node (ref "U16") (pin "136") (pinfunction "PB6_136") (pintype "bidirectional"))
      (node (ref "U5") (pin "1") (pinfunction "TXD_1") (pintype "bidirectional"))
    )
    (net (code "35") (name "CAN_TXD_3") (class "Default")
      (node (ref "U16") (pin "124") (pinfunction "PG9_124") (pintype "bidirectional"))
      (node (ref "U6") (pin "1") (pinfunction "TXD_1") (pintype "bidirectional"))
    )
    (net (code "36") (name "CAN_TXD_4") (class "Default")
      (node (ref "U16") (pin "74") (pinfunction "PB13_74") (pintype "bidirectional"))
      (node (ref "U7") (pin "1") (pinfunction "TXD_1") (pintype "bidirectional"))
    )
    (net (code "37") (name "CLK_555") (class "Default")
      (node (ref "IC3") (pin "3") (pinfunction "OUT_3") (pintype "output"))
      (node (ref "IC4") (pin "1") (pinfunction "1A_1") (pintype "input"))
      (node (ref "R32") (pin "1") (pinfunction "1_1") (pintype "passive"))
    )
    (net (code "38") (name "CLK_4040") (class "Default")
      (node (ref "IC2") (pin "10") (pinfunction "P1_10") (pintype "input"))
      (node (ref "IC4") (pin "6") (pinfunction "2Y_6") (pintype "output"))
    )
    (net (code "39") (name "CNT_RST") (class "Default")
      (node (ref "C4") (pin "2") (pinfunction "2_2") (pintype "passive"))
      (node (ref "IC2") (pin "11") (pinfunction "RES_11") (pintype "input"))
      (node (ref "R24") (pin "2") (pinfunction "2_2") (pintype "passive"))
    )
    (net (code "40") (name "GND") (class "Default")
      (node (ref "C1") (pin "2") (pinfunction "2_2") (pintype "passive"))
      (node (ref "C10") (pin "2") (pinfunction "2_2") (pintype "passive"))
      (node (ref "C11") (pin "2") (pinfunction "2_2") (pintype "passive"))
      (node (ref "C12") (pin "2") (pinfunction "2_2") (pintype "passive"))
      (node (ref "C2") (pin "2") (pinfunction "2_2") (pintype "passive"))
      (node (ref "C3") (pin "2") (pinfunction "2_2") (pintype "passive"))
      (node (ref "C38") (pin "2") (pinfunction "2_2") (pintype "passive"))
      (node (ref "C39") (pin "2") (pinfunction "2_2") (pintype "passive"))
      (node (ref "C40") (pin "2") (pinfunction "2_2") (pintype "passive"))
      (node (ref "C46") (pin "2") (pinfunction "2_2") (pintype "passive"))
      (node (ref "C47") (pin "2") (pinfunction "2_2") (pintype "passive"))
      (node (ref "C48") (pin "2") (pinfunction "2_2") (pintype "passive"))
      (node (ref "C49") (pin "2") (pinfunction "2_2") (pintype "passive"))
      (node (ref "C5") (pin "2") (pinfunction "2_2") (pintype "passive"))
      (node (ref "C50") (pin "2") (pinfunction "2_2") (pintype "passive"))
      (node (ref "C51") (pin "2") (pinfunction "2_2") (pintype "passive"))
      (node (ref "C52") (pin "2") (pinfunction "2_2") (pintype "passive"))
      (node (ref "C53") (pin "2") (pinfunction "2_2") (pintype "passive"))
      (node (ref "C54") (pin "2") (pinfunction "2_2") (pintype "passive"))
      (node (ref "C55") (pin "2") (pinfunction "2_2") (pintype "passive"))
      (node (ref "C56") (pin "2") (pinfunction "2_2") (pintype "passive"))
      (node (ref "C57") (pin "2") (pinfunction "2_2") (pintype "passive"))
      (node (ref "C59") (pin "2") (pinfunction "2_2") (pintype "passive"))
      (node (ref "C6") (pin "2") (pinfunction "2_2") (pintype "passive"))
      (node (ref "C60") (pin "2") (pinfunction "2_2") (pintype "passive"))
      (node (ref "C61") (pin "2") (pinfunction "2_2") (pintype "passive"))
      (node (ref "C69") (pin "2") (pinfunction "2_2") (pintype "passive"))
      (node (ref "C7") (pin "2") (pinfunction "2_2") (pintype "passive"))
      (node (ref "C70") (pin "2") (pinfunction "2_2") (pintype "passive"))
      (node (ref "C8") (pin "2") (pinfunction "2_2") (pintype "passive"))
      (node (ref "C9") (pin "2") (pinfunction "2_2") (pintype "passive"))
      (node (ref "D4") (pin "C") (pinfunction "C_C") (pintype "passive"))
      (node (ref "IC1") (pin "10") (pinfunction "P0B_10") (pintype "bidirectional"))
      (node (ref "IC1") (pin "4") (pinfunction "VSS_4") (pintype "power_in"))
      (node (ref "IC1") (pin "5") (pinfunction "P1B_5") (pintype "bidirectional"))
      (node (ref "IC2") (pin "8") (pinfunction "VSS_8") (pintype "power_in"))
      (node (ref "IC3") (pin "1") (pinfunction "GND_1") (pintype "bidirectional"))
      (node (ref "IC4") (pin "7") (pinfunction "GND_7") (pintype "bidirectional"))
      (node (ref "J1") (pin "5") (pinfunction "5_5") (pintype "passive"))
      (node (ref "J1") (pin "6") (pinfunction "6_6") (pintype "passive"))
      (node (ref "J11") (pin "1") (pinfunction "1_1") (pintype "passive"))
      (node (ref "J12") (pin "1") (pinfunction "1_1") (pintype "passive"))
      (node (ref "J13") (pin "A1") (pinfunction "GNDA1_A1") (pintype "power_in"))
      (node (ref "J13") (pin "A12") (pinfunction "GNDA2_A12") (pintype "power_in"))
      (node (ref "J13") (pin "B1") (pinfunction "GNDB1_B1") (pintype "power_in"))
      (node (ref "J13") (pin "B12") (pinfunction "GNDB2_B12") (pintype "power_in"))
      (node (ref "J13") (pin "G1") (pinfunction "GND/SHIELD_G1") (pintype "power_in"))
      (node (ref "J13") (pin "G2") (pinfunction "GND/SHIELD_G2") (pintype "power_in"))
      (node (ref "J13") (pin "G3") (pinfunction "GND/SHIELD_G3") (pintype "power_in"))
      (node (ref "J13") (pin "G4") (pinfunction "GND/SHIELD_G4") (pintype "power_in"))
      (node (ref "J13") (pin "S1") (pinfunction "GND/SHIELD_S1") (pintype "power_in"))
      (node (ref "J13") (pin "S2") (pinfunction "GND/SHIELD_S2") (pintype "power_in"))
      (node (ref "J13") (pin "S3") (pinfunction "GND/SHIELD_S3") (pintype "power_in"))
      (node (ref "J13") (pin "S4") (pinfunction "GND/SHIELD_S4") (pintype "power_in"))
      (node (ref "J6") (pin "GND") (pinfunction "GND_GND") (pintype "power_in"))
      (node (ref "J6") (pin "SHLD1") (pinfunction "SHIELD_SHLD1") (pintype "bidirectional"))
      (node (ref "J6") (pin "SHLD2") (pinfunction "SHIELD_SHLD2") (pintype "bidirectional"))
      (node (ref "JP5") (pin "1") (pinfunction "1_1") (pintype "passive"))
      (node (ref "Q12") (pin "2") (pinfunction "S_2") (pintype "bidirectional"))
      (node (ref "Q5") (pin "2") (pinfunction "S_2") (pintype "bidirectional"))
      (node (ref "Q6") (pin "2") (pinfunction "S_2") (pintype "bidirectional"))
      (node (ref "Q7") (pin "2") (pinfunction "S_2") (pintype "bidirectional"))
      (node (ref "Q8") (pin "2") (pinfunction "S_2") (pintype "bidirectional"))
      (node (ref "R1") (pin "1") (pinfunction "1_1") (pintype "passive"))
      (node (ref "R24") (pin "1") (pinfunction "1_1") (pintype "passive"))
      (node (ref "R27") (pin "1") (pinfunction "1_1") (pintype "passive"))
      (node (ref "R28") (pin "1") (pinfunction "1_1") (pintype "passive"))
      (node (ref "R29") (pin "1") (pinfunction "1_1") (pintype "passive"))
      (node (ref "R3") (pin "1") (pinfunction "1_1") (pintype "passive"))
      (node (ref "R38") (pin "1") (pinfunction "1_1") (pintype "passive"))
      (node (ref "SW1") (pin "1") (pinfunction "1_1") (pintype "passive"))
      (node (ref "U1") (pin "14") (pinfunction "GND_14") (pintype "power_in"))
      (node (ref "U1") (pin "20") (pinfunction "GND_20") (pintype "power_in"))
      (node (ref "U1") (pin "25") (pinfunction "GND_25") (pintype "power_in"))
      (node (ref "U1") (pin "30") (pinfunction "GND_30") (pintype "power_in"))
      (node (ref "U1") (pin "34") (pinfunction "GND_34") (pintype "power_in"))
      (node (ref "U1") (pin "39") (pinfunction "GND_39") (pintype "power_in"))
      (node (ref "U1") (pin "6") (pinfunction "GND_6") (pintype "power_in"))
      (node (ref "U1") (pin "9") (pinfunction "GND_9") (pintype "power_in"))
      (node (ref "U1") (pin "S1") (pinfunction "SHIELD_S1") (pintype "power_in"))
      (node (ref "U1") (pin "S2") (pinfunction "SHIELD_S2") (pintype "power_in"))
      (node (ref "U1") (pin "S3") (pinfunction "SHIELD_S3") (pintype "power_in"))
      (node (ref "U1") (pin "S4") (pinfunction "SHIELD_S4") (pintype "power_in"))
      (node (ref "U12") (pin "3") (pinfunction "3_3") (pintype "bidirectional"))
      (node (ref "U13") (pin "3") (pinfunction "3_3") (pintype "bidirectional"))
      (node (ref "U14") (pin "3") (pinfunction "3_3") (pintype "bidirectional"))
      (node (ref "U15") (pin "3") (pinfunction "3_3") (pintype "bidirectional"))
      (node (ref "U16") (pin "107") (pinfunction "VSS_107") (pintype "power_in"))
      (node (ref "U16") (pin "120") (pinfunction "VSS_120") (pintype "power_in"))
      (node (ref "U16") (pin "130") (pinfunction "VSS_130") (pintype "power_in"))
      (node (ref "U16") (pin "16") (pinfunction "VSS_16") (pintype "power_in"))
      (node (ref "U16") (pin "38") (pinfunction "VSS_38") (pintype "power_in"))
      (node (ref "U16") (pin "51") (pinfunction "VSS_51") (pintype "power_in"))
      (node (ref "U16") (pin "61") (pinfunction "VSS_61") (pintype "power_in"))
      (node (ref "U16") (pin "83") (pinfunction "VSS_83") (pintype "power_in"))
      (node (ref "U16") (pin "94") (pinfunction "VSS_94") (pintype "power_in"))
      (node (ref "U17") (pin "10") (pinfunction "P0B_10") (pintype "bidirectional"))
      (node (ref "U17") (pin "17") (pinfunction "EP_17") (pintype "bidirectional"))
      (node (ref "U17") (pin "3") (pinfunction "VSS_3") (pintype "power_in"))
      (node (ref "U17") (pin "4") (pinfunction "VSS-1_4") (pintype "power_in"))
      (node (ref "U17") (pin "5") (pinfunction "P1B_5") (pintype "bidirectional"))
      (node (ref "U2") (pin "2") (pinfunction "GND_2") (pintype "power_in"))
      (node (ref "U3") (pin "2") (pinfunction "GND_2") (pintype "power_in"))
      (node (ref "U3") (pin "7") (pinfunction "GND_EP_7") (pintype "power_in"))
      (node (ref "U4") (pin "2") (pinfunction "GND_2") (pintype "bidirectional"))
      (node (ref "U5") (pin "2") (pinfunction "GND_2") (pintype "bidirectional"))
      (node (ref "U6") (pin "2") (pinfunction "GND_2") (pintype "bidirectional"))
      (node (ref "U7") (pin "2") (pinfunction "GND_2") (pintype "bidirectional"))
      (node (ref "X1") (pin "2") (pinfunction "2_2") (pintype "passive"))
      (node (ref "X1") (pin "4") (pinfunction "4_4") (pintype "passive"))
    )
    (net (code "41") (name "LED_BLUE") (class "Default")
      (node (ref "R17") (pin "2") (pinfunction "2_2") (pintype "passive"))
      (node (ref "R29") (pin "2") (pinfunction "2_2") (pintype "passive"))
      (node (ref "U16") (pin "1") (pinfunction "PE2_1") (pintype "input"))
    )
    (net (code "42") (name "LED_GREEN") (class "Default")
      (node (ref "R18") (pin "2") (pinfunction "2_2") (pintype "passive"))
      (node (ref "R28") (pin "2") (pinfunction "2_2") (pintype "passive"))
      (node (ref "U16") (pin "2") (pinfunction "PE3_2") (pintype "bidirectional"))
    )
    (net (code "43") (name "LED_RED") (class "Default")
      (node (ref "R19") (pin "2") (pinfunction "2_2") (pintype "passive"))
      (node (ref "R27") (pin "2") (pinfunction "2_2") (pintype "passive"))
      (node (ref "U16") (pin "3") (pinfunction "PE4_3") (pintype "bidirectional"))
    )
    (net (code "44") (name "NRST") (class "Default")
      (node (ref "C59") (pin "1") (pinfunction "1_1") (pintype "passive"))
      (node (ref "J1") (pin "1") (pinfunction "1_1") (pintype "passive"))
      (node (ref "J7") (pin "4") (pinfunction "4_4") (pintype "bidirectional"))
      (node (ref "SW1") (pin "3") (pinfunction "2_3") (pintype "passive"))
      (node (ref "U16") (pin "25") (pinfunction "NRST_25") (pintype "bidirectional"))
    )
    (net (code "45") (name "Net-(D1-B_C)") (class "Default")
      (node (ref "D1") (pin "3") (pinfunction "B_C_3") (pintype "passive"))
      (node (ref "R12") (pin "1") (pinfunction "1_1") (pintype "passive"))
    )
    (net (code "46") (name "Net-(D1-G_C)") (class "Default")
      (node (ref "D1") (pin "4") (pinfunction "G_C_4") (pintype "passive"))
      (node (ref "R13") (pin "1") (pinfunction "1_1") (pintype "passive"))
    )
    (net (code "47") (name "Net-(D1-R_C)") (class "Default")
      (node (ref "D1") (pin "1") (pinfunction "R_C_1") (pintype "passive"))
      (node (ref "R14") (pin "1") (pinfunction "1_1") (pintype "passive"))
    )
    (net (code "48") (name "Net-(D2-A)") (class "Default")
      (node (ref "D2") (pin "2") (pinfunction "A_2") (pintype "passive"))
      (node (ref "K1") (pin "8") (pinfunction "-_8") (pintype "passive"))
      (node (ref "Q8") (pin "3") (pinfunction "D_3") (pintype "bidirectional"))
      (node (ref "R23") (pin "2") (pinfunction "2_2") (pintype "passive"))
    )
    (net (code "49") (name "Net-(D3-PadC)") (class "Default")
      (node (ref "D3") (pin "C") (pinfunction "C_C") (pintype "passive"))
      (node (ref "R23") (pin "1") (pinfunction "1_1") (pintype "passive"))
    )
    (net (code "50") (name "Net-(D4-PadA)") (class "Default")
      (node (ref "D4") (pin "A") (pinfunction "A_A") (pintype "passive"))
      (node (ref "R35") (pin "2") (pinfunction "2_2") (pintype "passive"))
    )
    (net (code "51") (name "Net-(D5-PadA)") (class "Default")
      (node (ref "D5") (pin "A") (pinfunction "A_A") (pintype "passive"))
      (node (ref "R36") (pin "2") (pinfunction "2_2") (pintype "passive"))
    )
    (net (code "52") (name "Net-(IC3-CV)") (class "Default")
      (node (ref "C2") (pin "1") (pinfunction "1_1") (pintype "passive"))
      (node (ref "IC3") (pin "5") (pinfunction "CV_5") (pintype "input"))
    )
    (net (code "53") (name "Net-(IC3-THR)") (class "Default")
      (node (ref "C1") (pin "1") (pinfunction "1_1") (pintype "passive"))
      (node (ref "IC3") (pin "2") (pinfunction "TR_2") (pintype "input"))
      (node (ref "IC3") (pin "6") (pinfunction "THR_6") (pintype "input"))
      (node (ref "R26") (pin "1") (pinfunction "1_1") (pintype "passive"))
      (node (ref "R32") (pin "2") (pinfunction "2_2") (pintype "passive"))
    )
    (net (code "54") (name "Net-(J1-Pad7)") (class "Default")
      (node (ref "J1") (pin "7") (pinfunction "7_7") (pintype "passive"))
      (node (ref "J1") (pin "8") (pinfunction "8_8") (pintype "passive"))
      (node (ref "J3") (pin "1") (pinfunction "1_1") (pintype "passive"))
    )
    (net (code "55") (name "Net-(J1-Pad10)") (class "Default")
      (node (ref "J1") (pin "10") (pinfunction "10_10") (pintype "passive"))
      (node (ref "J1") (pin "9") (pinfunction "9_9") (pintype "passive"))
      (node (ref "J4") (pin "1") (pinfunction "1_1") (pintype "passive"))
    )
    (net (code "56") (name "Net-(K1B-S)") (class "Default")
      (node (ref "J12") (pin "2") (pinfunction "2_2") (pintype "passive"))
      (node (ref "K1") (pin "4") (pinfunction "S_4") (pintype "passive"))
    )
    (net (code "57") (name "Net-(Q5-D)") (class "Default")
      (node (ref "Q5") (pin "3") (pinfunction "D_3") (pintype "bidirectional"))
      (node (ref "R12") (pin "2") (pinfunction "2_2") (pintype "passive"))
    )
    (net (code "58") (name "Net-(Q5-G)") (class "Default")
      (node (ref "Q5") (pin "1") (pinfunction "G_1") (pintype "bidirectional"))
      (node (ref "R17") (pin "1") (pinfunction "1_1") (pintype "passive"))
    )
    (net (code "59") (name "Net-(Q6-D)") (class "Default")
      (node (ref "Q6") (pin "3") (pinfunction "D_3") (pintype "bidirectional"))
      (node (ref "R13") (pin "2") (pinfunction "2_2") (pintype "passive"))
    )
    (net (code "60") (name "Net-(Q6-G)") (class "Default")
      (node (ref "Q6") (pin "1") (pinfunction "G_1") (pintype "bidirectional"))
      (node (ref "R18") (pin "1") (pinfunction "1_1") (pintype "passive"))
    )
    (net (code "61") (name "Net-(Q7-D)") (class "Default")
      (node (ref "Q7") (pin "3") (pinfunction "D_3") (pintype "bidirectional"))
      (node (ref "R14") (pin "2") (pinfunction "2_2") (pintype "passive"))
    )
    (net (code "62") (name "Net-(Q7-G)") (class "Default")
      (node (ref "Q7") (pin "1") (pinfunction "G_1") (pintype "bidirectional"))
      (node (ref "R19") (pin "1") (pinfunction "1_1") (pintype "passive"))
    )
    (net (code "63") (name "Net-(Q8-G)") (class "Default")
      (node (ref "Q8") (pin "1") (pinfunction "G_1") (pintype "bidirectional"))
      (node (ref "R22") (pin "1") (pinfunction "1_1") (pintype "passive"))
    )
    (net (code "64") (name "Net-(Q9-B)") (class "Default")
      (node (ref "Q9") (pin "1") (pinfunction "B_1") (pintype "passive"))
      (node (ref "R30") (pin "1") (pinfunction "1_1") (pintype "passive"))
    )
    (net (code "65") (name "Net-(Q10-B)") (class "Default")
      (node (ref "Q10") (pin "1") (pinfunction "B_1") (pintype "passive"))
      (node (ref "R31") (pin "1") (pinfunction "1_1") (pintype "passive"))
    )
    (net (code "66") (name "Net-(Q11-B)") (class "Default")
      (node (ref "Q11") (pin "1") (pinfunction "B_1") (pintype "passive"))
      (node (ref "R33") (pin "1") (pinfunction "1_1") (pintype "passive"))
    )
    (net (code "67") (name "Net-(Q12-G)") (class "Default")
      (node (ref "Q12") (pin "1") (pinfunction "G_1") (pintype "bidirectional"))
      (node (ref "R34") (pin "1") (pinfunction "1_1") (pintype "passive"))
    )
    (net (code "68") (name "Net-(U3-EN)") (class "Default")
      (node (ref "C38") (pin "1") (pinfunction "1_1") (pintype "passive"))
      (node (ref "R25") (pin "1") (pinfunction "1_1") (pintype "passive"))
      (node (ref "U3") (pin "1") (pinfunction "EN_1") (pintype "input"))
    )
    (net (code "69") (name "Net-(U3-VI)") (class "Default")
      (node (ref "C40") (pin "1") (pinfunction "1_1") (pintype "passive"))
      (node (ref "JP1") (pin "1") (pinfunction "1_1") (pintype "passive"))
      (node (ref "R25") (pin "2") (pinfunction "2_2") (pintype "passive"))
      (node (ref "U3") (pin "6") (pinfunction "VI_6") (pintype "input"))
    )
    (net (code "70") (name "Net-(U4-CAN_H)") (class "Default")
      (node (ref "U4") (pin "7") (pinfunction "CAN_H_7") (pintype "bidirectional"))
      (node (ref "U8") (pin "1") (pinfunction "1_1") (pintype "bidirectional"))
    )
    (net (code "71") (name "Net-(U4-CAN_L)") (class "Default")
      (node (ref "U4") (pin "6") (pinfunction "CAN_L_6") (pintype "bidirectional"))
      (node (ref "U8") (pin "2") (pinfunction "2_2") (pintype "bidirectional"))
    )
    (net (code "72") (name "Net-(U5-CAN_H)") (class "Default")
      (node (ref "U5") (pin "7") (pinfunction "CAN_H_7") (pintype "bidirectional"))
      (node (ref "U9") (pin "1") (pinfunction "1_1") (pintype "bidirectional"))
    )
    (net (code "73") (name "Net-(U5-CAN_L)") (class "Default")
      (node (ref "U5") (pin "6") (pinfunction "CAN_L_6") (pintype "bidirectional"))
      (node (ref "U9") (pin "2") (pinfunction "2_2") (pintype "bidirectional"))
    )
    (net (code "74") (name "Net-(U6-CAN_H)") (class "Default")
      (node (ref "U10") (pin "1") (pinfunction "1_1") (pintype "bidirectional"))
      (node (ref "U6") (pin "7") (pinfunction "CAN_H_7") (pintype "bidirectional"))
    )
    (net (code "75") (name "Net-(U6-CAN_L)") (class "Default")
      (node (ref "U10") (pin "2") (pinfunction "2_2") (pintype "bidirectional"))
      (node (ref "U6") (pin "6") (pinfunction "CAN_L_6") (pintype "bidirectional"))
    )
    (net (code "76") (name "Net-(U7-CAN_H)") (class "Default")
      (node (ref "U11") (pin "1") (pinfunction "1_1") (pintype "bidirectional"))
      (node (ref "U7") (pin "7") (pinfunction "CAN_H_7") (pintype "bidirectional"))
    )
    (net (code "77") (name "Net-(U7-CAN_L)") (class "Default")
      (node (ref "U11") (pin "2") (pinfunction "2_2") (pintype "bidirectional"))
      (node (ref "U7") (pin "6") (pinfunction "CAN_L_6") (pintype "bidirectional"))
    )
    (net (code "78") (name "Net-(U16-PA2)") (class "Default")
      (node (ref "J5") (pin "2") (pinfunction "2_2") (pintype "passive"))
      (node (ref "U16") (pin "36") (pinfunction "PA2_36") (pintype "bidirectional"))
    )
    (net (code "79") (name "Net-(U16-PA3)") (class "Default")
      (node (ref "J5") (pin "1") (pinfunction "1_1") (pintype "passive"))
      (node (ref "U16") (pin "37") (pinfunction "PA3_37") (pintype "bidirectional"))
    )
    (net (code "80") (name "OBD_SBU1") (class "Default")
      (node (ref "J13") (pin "A8") (pinfunction "SBU1_A8") (pintype "bidirectional"))
      (node (ref "Q9") (pin "3") (pinfunction "C_3") (pintype "passive"))
      (node (ref "R16") (pin "1") (pinfunction "1_1") (pintype "passive"))
      (node (ref "U16") (pin "44") (pinfunction "PC4_44") (pintype "bidirectional"))
    )
    (net (code "81") (name "OBD_SBU1_RELAY") (class "Default")
      (node (ref "R30") (pin "2") (pinfunction "2_2") (pintype "passive"))
      (node (ref "U16") (pin "111") (pinfunction "PC10_111") (pintype "bidirectional"))
    )
    (net (code "82") (name "OBD_SBU2") (class "Default")
      (node (ref "J13") (pin "B8") (pinfunction "SBU2_B8") (pintype "bidirectional"))
      (node (ref "Q10") (pin "3") (pinfunction "C_3") (pintype "passive"))
      (node (ref "R15") (pin "1") (pinfunction "1_1") (pintype "passive"))
      (node (ref "U16") (pin "35") (pinfunction "PA1_35") (pintype "bidirectional"))
    )
    (net (code "83") (name "OBD_SBU2_RELAY") (class "Default")
      (node (ref "R31") (pin "2") (pinfunction "2_2") (pintype "passive"))
      (node (ref "U16") (pin "112") (pinfunction "PC11_112") (pintype "bidirectional"))
    )
    (net (code "84") (name "PDR") (class "Default")
      (node (ref "R2") (pin "1") (pinfunction "1_1") (pintype "passive"))
      (node (ref "TP2") (pin "TP") (pinfunction "TP_TP") (pintype "passive"))
      (node (ref "U16") (pin "143") (pinfunction "PDR_ON_143") (pintype "bidirectional"))
    )
    (net (code "85") (name "PH0-OSC_IN") (class "Default")
      (node (ref "C69") (pin "1") (pinfunction "1_1") (pintype "passive"))
      (node (ref "U16") (pin "23") (pinfunction "PH0-OSC_IN_23") (pintype "bidirectional"))
      (node (ref "X1") (pin "3") (pinfunction "3_3") (pintype "passive"))
    )
    (net (code "86") (name "PH1-OSC_OUT") (class "Default")
      (node (ref "C70") (pin "1") (pinfunction "1_1") (pintype "passive"))
      (node (ref "U16") (pin "24") (pinfunction "PH0-OSC_OUT_24") (pintype "bidirectional"))
      (node (ref "X1") (pin "1") (pinfunction "1_1") (pintype "passive"))
    )
    (net (code "87") (name "PI_BOOT0") (class "Default")
      (node (ref "J7") (pin "5") (pinfunction "5_5") (pintype "bidirectional"))
      (node (ref "U1") (pin "13") (pinfunction "GPIO27/GPIO_GEN2_13") (pintype "bidirectional"))
    )
    (net (code "88") (name "PI_NRST") (class "Default")
      (node (ref "J7") (pin "6") (pinfunction "6_6") (pintype "bidirectional"))
      (node (ref "U1") (pin "11") (pinfunction "GPIO17/GPIO_GEN0_11") (pintype "bidirectional"))
    )
    (net (code "89") (name "POT_SHDN") (class "Default")
      (node (ref "IC1") (pin "12") (pinfunction "~{SHDN}_12") (pintype "input"))
      (node (ref "R20") (pin "1") (pinfunction "1_1") (pintype "passive"))
      (node (ref "U17") (pin "13") (pinfunction "~{SHDN}_13") (pintype "bidirectional"))
    )
    (net (code "90") (name "POT_WP") (class "Default")
      (node (ref "IC1") (pin "11") (pinfunction "~{WP}_11") (pintype "bidirectional"))
      (node (ref "R21") (pin "1") (pinfunction "1_1") (pintype "passive"))
      (node (ref "U17") (pin "12") (pinfunction "~{WP}_12") (pintype "bidirectional"))
    )
    (net (code "91") (name "RST_DRIVE") (class "Default")
      (node (ref "IC4") (pin "8") (pinfunction "3Y_8") (pintype "output"))
      (node (ref "R34") (pin "2") (pinfunction "2_2") (pintype "passive"))
      (node (ref "R35") (pin "1") (pinfunction "1_1") (pintype "passive"))
    )
    (net (code "92") (name "R_EN") (class "Default")
      (node (ref "R22") (pin "2") (pinfunction "2_2") (pintype "passive"))
      (node (ref "R3") (pin "2") (pinfunction "2_2") (pintype "passive"))
      (node (ref "U1") (pin "36") (pinfunction "GPIO16_36") (pintype "bidirectional"))
    )
    (net (code "93") (name "R_OUT") (class "Default")
      (node (ref "IC1") (pin "6") (pinfunction "P1W_6") (pintype "bidirectional"))
      (node (ref "IC1") (pin "9") (pinfunction "P0W_9") (pintype "bidirectional"))
      (node (ref "K1") (pin "3") (pinfunction "P_3") (pintype "passive"))
      (node (ref "U17") (pin "6") (pinfunction "P1W_6") (pintype "bidirectional"))
      (node (ref "U17") (pin "9") (pinfunction "P0W_9") (pintype "bidirectional"))
    )
    (net (code "94") (name "SPI_CLK_HV") (class "Default")
      (node (ref "IC1") (pin "2") (pinfunction "SCK_2") (pintype "input"))
      (node (ref "Q2") (pin "3") (pinfunction "D_3") (pintype "bidirectional"))
      (node (ref "R7") (pin "1") (pinfunction "1_1") (pintype "passive"))
      (node (ref "U17") (pin "1") (pinfunction "SCK_1") (pintype "bidirectional"))
    )
    (net (code "95") (name "SPI_CLK_LV") (class "Default")
      (node (ref "Q2") (pin "2") (pinfunction "S_2") (pintype "bidirectional"))
      (node (ref "R6") (pin "1") (pinfunction "1_1") (pintype "passive"))
      (node (ref "U1") (pin "23") (pinfunction "GPIO11/SPI_SCLK_23") (pintype "bidirectional"))
    )
    (net (code "96") (name "SPI_CS_HV") (class "Default")
      (node (ref "IC1") (pin "1") (pinfunction "~{CS}_1") (pintype "input"))
      (node (ref "Q1") (pin "3") (pinfunction "D_3") (pintype "bidirectional"))
      (node (ref "R5") (pin "1") (pinfunction "1_1") (pintype "passive"))
      (node (ref "U17") (pin "16") (pinfunction "~{CS}_16") (pintype "bidirectional"))
    )
    (net (code "97") (name "SPI_CS_LV") (class "Default")
      (node (ref "Q1") (pin "2") (pinfunction "S_2") (pintype "bidirectional"))
      (node (ref "R4") (pin "1") (pinfunction "1_1") (pintype "passive"))
      (node (ref "U1") (pin "24") (pinfunction "GPIO8/~{SPI_CE0}_24") (pintype "bidirectional"))
    )
    (net (code "98") (name "SPI_MISO_HV") (class "Default")
      (node (ref "IC1") (pin "13") (pinfunction "SDO_13") (pintype "bidirectional"))
      (node (ref "Q4") (pin "3") (pinfunction "D_3") (pintype "bidirectional"))
      (node (ref "R11") (pin "1") (pinfunction "1_1") (pintype "passive"))
      (node (ref "U17") (pin "14") (pinfunction "SDO_14") (pintype "bidirectional"))
    )
    (net (code "99") (name "SPI_MISO_LV") (class "Default")
      (node (ref "Q4") (pin "2") (pinfunction "S_2") (pintype "bidirectional"))
      (node (ref "R10") (pin "1") (pinfunction "1_1") (pintype "passive"))
      (node (ref "U1") (pin "21") (pinfunction "GPIO9/SPI_MISO_21") (pintype "bidirectional"))
    )
    (net (code "100") (name "SPI_MOSI_HV") (class "Default")
      (node (ref "IC1") (pin "3") (pinfunction "SDI_3") (pintype "input"))
      (node (ref "Q3") (pin "3") (pinfunction "D_3") (pintype "bidirectional"))
      (node (ref "R9") (pin "1") (pinfunction "1_1") (pintype "passive"))
      (node (ref "U17") (pin "2") (pinfunction "SDI_2") (pintype "input"))
    )
    (net (code "101") (name "SPI_MOSI_LV") (class "Default")
      (node (ref "Q3") (pin "2") (pinfunction "S_2") (pintype "bidirectional"))
      (node (ref "R8") (pin "1") (pinfunction "1_1") (pintype "passive"))
      (node (ref "U1") (pin "19") (pinfunction "GPIO10/SPI_MOSI_19") (pintype "bidirectional"))
    )
    (net (code "102") (name "SWCLK") (class "Default")
      (node (ref "J1") (pin "2") (pinfunction "2_2") (pintype "passive"))
      (node (ref "U16") (pin "109") (pinfunction "PA14_109") (pintype "bidirectional"))
    )
    (net (code "103") (name "SWDIO") (class "Default")
      (node (ref "J1") (pin "4") (pinfunction "4_4") (pintype "passive"))
      (node (ref "U16") (pin "105") (pinfunction "PA13_105") (pintype "bidirectional"))
    )
    (net (code "104") (name "SWO-SWIM") (class "Default")
      (node (ref "J1") (pin "3") (pinfunction "3_3") (pintype "passive"))
      (node (ref "J2") (pin "1") (pinfunction "1_1") (pintype "passive"))
    )
    (net (code "105") (name "USB_DN") (class "Default")
      (node (ref "J6") (pin "D-") (pinfunction "D-_D-") (pintype "bidirectional"))
      (node (ref "U16") (pin "103") (pinfunction "PA11_103") (pintype "bidirectional"))
      (node (ref "U2") (pin "3") (pinfunction "IO2_3") (pintype "bidirectional"))
    )
    (net (code "106") (name "USB_DP") (class "Default")
      (node (ref "J6") (pin "D+") (pinfunction "D+_D+") (pintype "bidirectional"))
      (node (ref "U16") (pin "104") (pinfunction "PA12_104") (pintype "bidirectional"))
      (node (ref "U2") (pin "1") (pinfunction "IO1_1") (pintype "bidirectional"))
    )
    (net (code "107") (name "USB_ID") (class "Default")
      (node (ref "TP3") (pin "TP") (pinfunction "TP_TP") (pintype "passive"))
      (node (ref "U16") (pin "102") (pinfunction "PA10_102") (pintype "bidirectional"))
    )
    (net (code "108") (name "USB_LOAD_SWITCH") (class "Default")
      (node (ref "TP1") (pin "TP") (pinfunction "TP_TP") (pintype "passive"))
      (node (ref "U16") (pin "75") (pinfunction "PB14_75") (pintype "bidirectional"))
    )
    (net (code "109") (name "VBAT") (class "Default")
      (node (ref "C61") (pin "1") (pinfunction "1_1") (pintype "passive"))
      (node (ref "JP4") (pin "2") (pinfunction "2_2") (pintype "passive"))
      (node (ref "U16") (pin "6") (pinfunction "VBAT_6") (pintype "power_in"))
    )
    (net (code "110") (name "VCAP") (class "Default")
      (node (ref "C48") (pin "1") (pinfunction "1_1") (pintype "passive"))
      (node (ref "C50") (pin "1") (pinfunction "1_1") (pintype "passive"))
      (node (ref "U16") (pin "106") (pinfunction "VCAP_106") (pintype "bidirectional"))
      (node (ref "U16") (pin "71") (pinfunction "VCAP_71") (pintype "bidirectional"))
    )
    (net (code "111") (name "VDDA") (class "Default")
      (node (ref "C66") (pin "1") (pinfunction "1_1") (pintype "passive"))
      (node (ref "C67") (pin "1") (pinfunction "1_1") (pintype "passive"))
      (node (ref "JP2") (pin "1") (pinfunction "1_1") (pintype "passive"))
      (node (ref "JP3") (pin "2") (pinfunction "2_2") (pintype "passive"))
      (node (ref "U16") (pin "33") (pinfunction "VDDA_33") (pintype "power_in"))
    )
    (net (code "112") (name "VHAX") (class "Default")
      (node (ref "C4") (pin "1") (pinfunction "1_1") (pintype "passive"))
      (node (ref "IC2") (pin "16") (pinfunction "VDD_16") (pintype "power_in"))
      (node (ref "IC3") (pin "4") (pinfunction "~{RST}_4") (pintype "input"))
      (node (ref "IC3") (pin "8") (pinfunction "V+_8") (pintype "bidirectional"))
      (node (ref "IC4") (pin "14") (pinfunction "VCC_14") (pintype "bidirectional"))
      (node (ref "JP6") (pin "2") (pinfunction "2_2") (pintype "passive"))
      (node (ref "Q11") (pin "2") (pinfunction "E_2") (pintype "passive"))
      (node (ref "R26") (pin "2") (pinfunction "2_2") (pintype "passive"))
      (node (ref "R36") (pin "1") (pinfunction "1_1") (pintype "passive"))
    )
    (net (code "113") (name "VIN") (class "Default")
      (node (ref "J11") (pin "2") (pinfunction "2_2") (pintype "passive"))
      (node (ref "J13") (pin "A4") (pinfunction "VBUSA1_A4") (pintype "power_in"))
      (node (ref "J13") (pin "A9") (pinfunction "VBUSA2_A9") (pintype "power_in"))
      (node (ref "J13") (pin "B4") (pinfunction "VBUSB1_B4") (pintype "power_in"))
      (node (ref "J13") (pin "B9") (pinfunction "VBUSB2_B9") (pintype "power_in"))
      (node (ref "R37") (pin "2") (pinfunction "2_2") (pintype "passive"))
    )
    (net (code "114") (name "VOLT_S") (class "Default")
      (node (ref "C3") (pin "1") (pinfunction "1_1") (pintype "passive"))
      (node (ref "R37") (pin "1") (pinfunction "1_1") (pintype "passive"))
      (node (ref "R38") (pin "2") (pinfunction "2_2") (pintype "passive"))
      (node (ref "TP5") (pin "TP") (pinfunction "TP_TP") (pintype "passive"))
      (node (ref "U16") (pin "49") (pinfunction "PF11_49") (pintype "bidirectional"))
    )
    (net (code "115") (name "VREFP") (class "Default")
      (node (ref "C58") (pin "1") (pinfunction "1_1") (pintype "passive"))
      (node (ref "C64") (pin "1") (pinfunction "1_1") (pintype "passive"))
      (node (ref "C65") (pin "1") (pinfunction "1_1") (pintype "passive"))
      (node (ref "JP2") (pin "2") (pinfunction "2_2") (pintype "passive"))
      (node (ref "U16") (pin "32") (pinfunction "VREF+_32") (pintype "input"))
    )
    (net (code "116") (name "X728_BOOT") (class "Default")
      (node (ref "U1") (pin "32") (pinfunction "GPIO12_32") (pintype "bidirectional"))
    )
    (net (code "117") (name "X728_BUTTON") (class "Default")
      (node (ref "U1") (pin "37") (pinfunction "GPIO26_37") (pintype "bidirectional"))
    )
    (net (code "118") (name "X728_BUZZER") (class "Default")
      (node (ref "U1") (pin "38") (pinfunction "GPIO20_38") (pintype "bidirectional"))
    )
    (net (code "119") (name "X728_PLD") (class "Default")
      (node (ref "U1") (pin "31") (pinfunction "GPIO6_31") (pintype "bidirectional"))
    )
    (net (code "120") (name "X728_SHUTDOWN") (class "Default")
      (node (ref "U1") (pin "29") (pinfunction "GPIO5_29") (pintype "bidirectional"))
    )
    (net (code "121") (name "unconnected-(IC1-P0A-Pad8)") (class "Default")
      (node (ref "IC1") (pin "8") (pinfunction "P0A_8") (pintype "bidirectional"))
    )
    (net (code "122") (name "unconnected-(IC1-P1A-Pad7)") (class "Default")
      (node (ref "IC1") (pin "7") (pinfunction "P1A_7") (pintype "bidirectional"))
    )
    (net (code "123") (name "unconnected-(IC2A-Q1-Pad9)") (class "Default")
      (node (ref "IC2") (pin "9") (pinfunction "Q1_9") (pintype "output"))
    )
    (net (code "124") (name "unconnected-(IC2A-Q2-Pad7)") (class "Default")
      (node (ref "IC2") (pin "7") (pinfunction "Q2_7") (pintype "output"))
    )
    (net (code "125") (name "unconnected-(IC2A-Q3-Pad6)") (class "Default")
      (node (ref "IC2") (pin "6") (pinfunction "Q3_6") (pintype "output"))
    )
    (net (code "126") (name "unconnected-(IC2A-Q4-Pad5)") (class "Default")
      (node (ref "IC2") (pin "5") (pinfunction "Q4_5") (pintype "output"))
    )
    (net (code "127") (name "unconnected-(IC2A-Q5-Pad3)") (class "Default")
      (node (ref "IC2") (pin "3") (pinfunction "Q5_3") (pintype "output"))
    )
    (net (code "128") (name "unconnected-(IC2A-Q8-Pad13)") (class "Default")
      (node (ref "IC2") (pin "13") (pinfunction "Q8_13") (pintype "output"))
    )
    (net (code "129") (name "unconnected-(IC2A-Q9-Pad12)") (class "Default")
      (node (ref "IC2") (pin "12") (pinfunction "Q9_12") (pintype "output"))
    )
    (net (code "130") (name "unconnected-(IC2A-Q10-Pad14)") (class "Default")
      (node (ref "IC2") (pin "14") (pinfunction "Q10_14") (pintype "output"))
    )
    (net (code "131") (name "unconnected-(IC2A-Q11-Pad15)") (class "Default")
      (node (ref "IC2") (pin "15") (pinfunction "Q11_15") (pintype "output"))
    )
    (net (code "132") (name "unconnected-(IC2A-Q12-Pad1)") (class "Default")
      (node (ref "IC2") (pin "1") (pinfunction "Q12_1") (pintype "output"))
    )
    (net (code "133") (name "unconnected-(IC3-DIS-Pad7)") (class "Default")
      (node (ref "IC3") (pin "7") (pinfunction "DIS_7") (pintype "input"))
    )
    (net (code "134") (name "unconnected-(J13-CC1-PadA5)") (class "Default")
      (node (ref "J13") (pin "A5") (pinfunction "CC1_A5") (pintype "bidirectional"))
    )
    (net (code "135") (name "unconnected-(J13-CC2-PadB5)") (class "Default")
      (node (ref "J13") (pin "B5") (pinfunction "CC2_B5") (pintype "bidirectional"))
    )
    (net (code "136") (name "unconnected-(J13-DN1-PadA7)") (class "Default")
      (node (ref "J13") (pin "A7") (pinfunction "DN1_A7") (pintype "bidirectional"))
    )
    (net (code "137") (name "unconnected-(J13-DN2-PadB7)") (class "Default")
      (node (ref "J13") (pin "B7") (pinfunction "DN2_B7") (pintype "bidirectional"))
    )
    (net (code "138") (name "unconnected-(J13-DP1-PadA6)") (class "Default")
      (node (ref "J13") (pin "A6") (pinfunction "DP1_A6") (pintype "bidirectional"))
    )
    (net (code "139") (name "unconnected-(J13-DP2-PadB6)") (class "Default")
      (node (ref "J13") (pin "B6") (pinfunction "DP2_B6") (pintype "bidirectional"))
    )
    (net (code "140") (name "unconnected-(K1B-O-Pad2)") (class "Default")
      (node (ref "K1") (pin "2") (pinfunction "O_2") (pintype "passive"))
    )
    (net (code "141") (name "unconnected-(K1C-O-Pad7)") (class "Default")
      (node (ref "K1") (pin "7") (pinfunction "O_7") (pintype "passive"))
    )
    (net (code "142") (name "unconnected-(K1C-P-Pad6)") (class "Default")
      (node (ref "K1") (pin "6") (pinfunction "P_6") (pintype "passive"))
    )
    (net (code "143") (name "unconnected-(K1C-S-Pad5)") (class "Default")
      (node (ref "K1") (pin "5") (pinfunction "S_5") (pintype "passive"))
    )
    (net (code "144") (name "unconnected-(U1-GPIO2{slash}SDA1-Pad3)") (class "Default")
      (node (ref "U1") (pin "3") (pinfunction "GPIO2/SDA1_3") (pintype "bidirectional"))
    )
    (net (code "145") (name "unconnected-(U1-GPIO3{slash}SCL1-Pad5)") (class "Default")
      (node (ref "U1") (pin "5") (pinfunction "GPIO3/SCL1_5") (pintype "bidirectional"))
    )
    (net (code "146") (name "unconnected-(U1-GPIO4{slash}GPIO_GCKL-Pad7)") (class "Default")
      (node (ref "U1") (pin "7") (pinfunction "GPIO4/GPIO_GCKL_7") (pintype "bidirectional"))
    )
    (net (code "147") (name "unconnected-(U1-GPIO7{slash}~{SPI_CE1}-Pad26)") (class "Default")
      (node (ref "U1") (pin "26") (pinfunction "GPIO7/~{SPI_CE1}_26") (pintype "bidirectional"))
    )
    (net (code "148") (name "unconnected-(U1-GPIO13-Pad33)") (class "Default")
      (node (ref "U1") (pin "33") (pinfunction "GPIO13_33") (pintype "bidirectional"))
    )
    (net (code "149") (name "unconnected-(U1-GPIO18{slash}GPIO_GEN1-Pad12)") (class "Default")
      (node (ref "U1") (pin "12") (pinfunction "GPIO18/GPIO_GEN1_12") (pintype "bidirectional"))
    )
    (net (code "150") (name "unconnected-(U1-GPIO19-Pad35)") (class "Default")
      (node (ref "U1") (pin "35") (pinfunction "GPIO19_35") (pintype "bidirectional"))
    )
    (net (code "151") (name "unconnected-(U1-GPIO21-Pad40)") (class "Default")
      (node (ref "U1") (pin "40") (pinfunction "GPIO21_40") (pintype "bidirectional"))
    )
    (net (code "152") (name "unconnected-(U1-GPIO22{slash}GPIO_GEN3-Pad15)") (class "Default")
      (node (ref "U1") (pin "15") (pinfunction "GPIO22/GPIO_GEN3_15") (pintype "bidirectional"))
    )
    (net (code "153") (name "unconnected-(U1-GPIO23{slash}GPIO_GEN4-Pad16)") (class "Default")
      (node (ref "U1") (pin "16") (pinfunction "GPIO23/GPIO_GEN4_16") (pintype "bidirectional"))
    )
    (net (code "154") (name "unconnected-(U1-GPIO24{slash}GPIO_GEN5-Pad18)") (class "Default")
      (node (ref "U1") (pin "18") (pinfunction "GPIO24/GPIO_GEN5_18") (pintype "bidirectional"))
    )
    (net (code "155") (name "unconnected-(U1-GPIO25{slash}GPIO_GEN6-Pad22)") (class "Default")
      (node (ref "U1") (pin "22") (pinfunction "GPIO25/GPIO_GEN6_22") (pintype "bidirectional"))
    )
    (net (code "156") (name "unconnected-(U1-ID_SC-Pad28)") (class "Default")
      (node (ref "U1") (pin "28") (pinfunction "ID_SC_28") (pintype "bidirectional"))
    )
    (net (code "157") (name "unconnected-(U1-ID_SD-Pad27)") (class "Default")
      (node (ref "U1") (pin "27") (pinfunction "ID_SD_27") (pintype "bidirectional"))
    )
    (net (code "158") (name "unconnected-(U1-RXD0{slash}GPIO15-Pad10)") (class "Default")
      (node (ref "U1") (pin "10") (pinfunction "RXD0/GPIO15_10") (pintype "bidirectional"))
    )
    (net (code "159") (name "unconnected-(U1-TXD0{slash}GPIO14-Pad8)") (class "Default")
      (node (ref "U1") (pin "8") (pinfunction "TXD0/GPIO14_8") (pintype "bidirectional"))
    )
    (net (code "160") (name "unconnected-(U2-IO3-Pad4)") (class "Default")
      (node (ref "U2") (pin "4") (pinfunction "IO3_4") (pintype "bidirectional"))
    )
    (net (code "161") (name "unconnected-(U2-IO4-Pad6)") (class "Default")
      (node (ref "U2") (pin "6") (pinfunction "IO4_6") (pintype "bidirectional"))
    )
    (net (code "162") (name "unconnected-(U3-NC-Pad3)") (class "Default")
      (node (ref "U3") (pin "3") (pinfunction "NC_3") (pintype "bidirectional"))
    )
    (net (code "163") (name "unconnected-(U16-PA0-Pad34)") (class "Default")
      (node (ref "U16") (pin "34") (pinfunction "PA0_34") (pintype "bidirectional"))
    )
    (net (code "164") (name "unconnected-(U16-PA4-Pad40)") (class "Default")
      (node (ref "U16") (pin "40") (pinfunction "PA4_40") (pintype "bidirectional"))
    )
    (net (code "165") (name "unconnected-(U16-PA5-Pad41)") (class "Default")
      (node (ref "U16") (pin "41") (pinfunction "PA5_41") (pintype "bidirectional"))
    )
    (net (code "166") (name "unconnected-(U16-PA6-Pad42)") (class "Default")
      (node (ref "U16") (pin "42") (pinfunction "PA6_42") (pintype "bidirectional"))
    )
    (net (code "167") (name "unconnected-(U16-PA7-Pad43)") (class "Default")
      (node (ref "U16") (pin "43") (pinfunction "PA7_43") (pintype "bidirectional"))
    )
    (net (code "168") (name "unconnected-(U16-PA8-Pad100)") (class "Default")
      (node (ref "U16") (pin "100") (pinfunction "PA8_100") (pintype "bidirectional"))
    )
    (net (code "169") (name "unconnected-(U16-PA9-Pad101)") (class "Default")
      (node (ref "U16") (pin "101") (pinfunction "PA9_101") (pintype "bidirectional"))
    )
    (net (code "170") (name "unconnected-(U16-PA15-Pad110)") (class "Default")
      (node (ref "U16") (pin "110") (pinfunction "PA15_110") (pintype "bidirectional"))
    )
    (net (code "171") (name "unconnected-(U16-PB0-Pad46)") (class "Default")
      (node (ref "U16") (pin "46") (pinfunction "PB0_46") (pintype "bidirectional"))
    )
    (net (code "172") (name "unconnected-(U16-PB2-Pad48)") (class "Default")
      (node (ref "U16") (pin "48") (pinfunction "PB2_48") (pintype "bidirectional"))
    )
    (net (code "173") (name "unconnected-(U16-PB7-Pad137)") (class "Default")
      (node (ref "U16") (pin "137") (pinfunction "PB7_137") (pintype "bidirectional"))
    )
    (net (code "174") (name "unconnected-(U16-PB10-Pad69)") (class "Default")
      (node (ref "U16") (pin "69") (pinfunction "PB10_69") (pintype "bidirectional"))
    )
    (net (code "175") (name "unconnected-(U16-PB11-Pad70)") (class "Default")
      (node (ref "U16") (pin "70") (pinfunction "PB11_70") (pintype "bidirectional"))
    )
    (net (code "176") (name "unconnected-(U16-PB15-Pad76)") (class "Default")
      (node (ref "U16") (pin "76") (pinfunction "PB15_76") (pintype "bidirectional"))
    )
    (net (code "177") (name "unconnected-(U16-PC0-Pad26)") (class "Default")
      (node (ref "U16") (pin "26") (pinfunction "PC0_26") (pintype "bidirectional"))
    )
    (net (code "178") (name "unconnected-(U16-PC1-Pad27)") (class "Default")
      (node (ref "U16") (pin "27") (pinfunction "PC1_27") (pintype "bidirectional"))
    )
    (net (code "179") (name "unconnected-(U16-PC2_C-Pad28)") (class "Default")
      (node (ref "U16") (pin "28") (pinfunction "PC2_C_28") (pintype "bidirectional"))
    )
    (net (code "180") (name "unconnected-(U16-PC3_C-Pad29)") (class "Default")
      (node (ref "U16") (pin "29") (pinfunction "PC3_C_29") (pintype "bidirectional"))
    )
    (net (code "181") (name "unconnected-(U16-PC5-Pad45)") (class "Default")
      (node (ref "U16") (pin "45") (pinfunction "PC5_45") (pintype "bidirectional"))
    )
    (net (code "182") (name "unconnected-(U16-PC6-Pad96)") (class "Default")
      (node (ref "U16") (pin "96") (pinfunction "PC6_96") (pintype "bidirectional"))
    )
    (net (code "183") (name "unconnected-(U16-PC7-Pad97)") (class "Default")
      (node (ref "U16") (pin "97") (pinfunction "PC7_97") (pintype "bidirectional"))
    )
    (net (code "184") (name "unconnected-(U16-PC8-Pad98)") (class "Default")
      (node (ref "U16") (pin "98") (pinfunction "PC8_98") (pintype "bidirectional"))
    )
    (net (code "185") (name "unconnected-(U16-PC9-Pad99)") (class "Default")
      (node (ref "U16") (pin "99") (pinfunction "PC9_99") (pintype "bidirectional"))
    )
    (net (code "186") (name "unconnected-(U16-PC12-Pad113)") (class "Default")
      (node (ref "U16") (pin "113") (pinfunction "PC12_113") (pintype "bidirectional"))
    )
    (net (code "187") (name "unconnected-(U16-PC13-Pad7)") (class "Default")
      (node (ref "U16") (pin "7") (pinfunction "PC13_7") (pintype "bidirectional"))
    )
    (net (code "188") (name "unconnected-(U16-PC14-OSC32_IN-Pad8)") (class "Default")
      (node (ref "U16") (pin "8") (pinfunction "PC14-OSC32_IN_8") (pintype "bidirectional"))
    )
    (net (code "189") (name "unconnected-(U16-PC15-OSC32_OUT-Pad9)") (class "Default")
      (node (ref "U16") (pin "9") (pinfunction "PC15-OSC32_OUT_9") (pintype "bidirectional"))
    )
    (net (code "190") (name "unconnected-(U16-PD0-Pad114)") (class "Default")
      (node (ref "U16") (pin "114") (pinfunction "PD0_114") (pintype "bidirectional"))
    )
    (net (code "191") (name "unconnected-(U16-PD1-Pad115)") (class "Default")
      (node (ref "U16") (pin "115") (pinfunction "PD1_115") (pintype "bidirectional"))
    )
    (net (code "192") (name "unconnected-(U16-PD2-Pad116)") (class "Default")
      (node (ref "U16") (pin "116") (pinfunction "PD2_116") (pintype "bidirectional"))
    )
    (net (code "193") (name "unconnected-(U16-PD3-Pad117)") (class "Default")
      (node (ref "U16") (pin "117") (pinfunction "PD3_117") (pintype "bidirectional"))
    )
    (net (code "194") (name "unconnected-(U16-PD4-Pad118)") (class "Default")
      (node (ref "U16") (pin "118") (pinfunction "PD4_118") (pintype "bidirectional"))
    )
    (net (code "195") (name "unconnected-(U16-PD5-Pad119)") (class "Default")
      (node (ref "U16") (pin "119") (pinfunction "PD5_119") (pintype "bidirectional"))
    )
    (net (code "196") (name "unconnected-(U16-PD6-Pad122)") (class "Default")
      (node (ref "U16") (pin "122") (pinfunction "PD6_122") (pintype "bidirectional"))
    )
    (net (code "197") (name "unconnected-(U16-PD8-Pad77)") (class "Default")
      (node (ref "U16") (pin "77") (pinfunction "PD8_77") (pintype "bidirectional"))
    )
    (net (code "198") (name "unconnected-(U16-PD9-Pad78)") (class "Default")
      (node (ref "U16") (pin "78") (pinfunction "PD9_78") (pintype "bidirectional"))
    )
    (net (code "199") (name "unconnected-(U16-PD10-Pad79)") (class "Default")
      (node (ref "U16") (pin "79") (pinfunction "PD10_79") (pintype "bidirectional"))
    )
    (net (code "200") (name "unconnected-(U16-PD11-Pad80)") (class "Default")
      (node (ref "U16") (pin "80") (pinfunction "PD11_80") (pintype "bidirectional"))
    )
    (net (code "201") (name "unconnected-(U16-PD12-Pad81)") (class "Default")
      (node (ref "U16") (pin "81") (pinfunction "PD12_81") (pintype "bidirectional"))
    )
    (net (code "202") (name "unconnected-(U16-PD13-Pad82)") (class "Default")
      (node (ref "U16") (pin "82") (pinfunction "PD13_82") (pintype "bidirectional"))
    )
    (net (code "203") (name "unconnected-(U16-PD14-Pad85)") (class "Default")
      (node (ref "U16") (pin "85") (pinfunction "PD14_85") (pintype "bidirectional"))
    )
    (net (code "204") (name "unconnected-(U16-PD15-Pad86)") (class "Default")
      (node (ref "U16") (pin "86") (pinfunction "PD15_86") (pintype "bidirectional"))
    )
    (net (code "205") (name "unconnected-(U16-PE0-Pad141)") (class "Default")
      (node (ref "U16") (pin "141") (pinfunction "PE0_141") (pintype "bidirectional"))
    )
    (net (code "206") (name "unconnected-(U16-PE1-Pad142)") (class "Default")
      (node (ref "U16") (pin "142") (pinfunction "PE1_142") (pintype "bidirectional"))
    )
    (net (code "207") (name "unconnected-(U16-PE5-Pad4)") (class "Default")
      (node (ref "U16") (pin "4") (pinfunction "PE5_4") (pintype "bidirectional"))
    )
    (net (code "208") (name "unconnected-(U16-PE6-Pad5)") (class "Default")
      (node (ref "U16") (pin "5") (pinfunction "PE6_5") (pintype "bidirectional"))
    )
    (net (code "209") (name "unconnected-(U16-PE7-Pad58)") (class "Default")
      (node (ref "U16") (pin "58") (pinfunction "PE7_58") (pintype "bidirectional"))
    )
    (net (code "210") (name "unconnected-(U16-PE8-Pad59)") (class "Default")
      (node (ref "U16") (pin "59") (pinfunction "PE8_59") (pintype "bidirectional"))
    )
    (net (code "211") (name "unconnected-(U16-PE9-Pad60)") (class "Default")
      (node (ref "U16") (pin "60") (pinfunction "PE9_60") (pintype "bidirectional"))
    )
    (net (code "212") (name "unconnected-(U16-PE10-Pad63)") (class "Default")
      (node (ref "U16") (pin "63") (pinfunction "PE10_63") (pintype "bidirectional"))
    )
    (net (code "213") (name "unconnected-(U16-PE11-Pad64)") (class "Default")
      (node (ref "U16") (pin "64") (pinfunction "PE11_64") (pintype "bidirectional"))
    )
    (net (code "214") (name "unconnected-(U16-PE12-Pad65)") (class "Default")
      (node (ref "U16") (pin "65") (pinfunction "PE12_65") (pintype "bidirectional"))
    )
    (net (code "215") (name "unconnected-(U16-PE13-Pad66)") (class "Default")
      (node (ref "U16") (pin "66") (pinfunction "PE13_66") (pintype "bidirectional"))
    )
    (net (code "216") (name "unconnected-(U16-PE14-Pad67)") (class "Default")
      (node (ref "U16") (pin "67") (pinfunction "PE14_67") (pintype "bidirectional"))
    )
    (net (code "217") (name "unconnected-(U16-PE15-Pad68)") (class "Default")
      (node (ref "U16") (pin "68") (pinfunction "PE15_68") (pintype "bidirectional"))
    )
    (net (code "218") (name "unconnected-(U16-PF0-Pad10)") (class "Default")
      (node (ref "U16") (pin "10") (pinfunction "PF0_10") (pintype "bidirectional"))
    )
    (net (code "219") (name "unconnected-(U16-PF1-Pad11)") (class "Default")
      (node (ref "U16") (pin "11") (pinfunction "PF1_11") (pintype "bidirectional"))
    )
    (net (code "220") (name "unconnected-(U16-PF2-Pad12)") (class "Default")
      (node (ref "U16") (pin "12") (pinfunction "PF2_12") (pintype "bidirectional"))
    )
    (net (code "221") (name "unconnected-(U16-PF3-Pad13)") (class "Default")
      (node (ref "U16") (pin "13") (pinfunction "PF3_13") (pintype "bidirectional"))
    )
    (net (code "222") (name "unconnected-(U16-PF4-Pad14)") (class "Default")
      (node (ref "U16") (pin "14") (pinfunction "PF4_14") (pintype "bidirectional"))
    )
    (net (code "223") (name "unconnected-(U16-PF5-Pad15)") (class "Default")
      (node (ref "U16") (pin "15") (pinfunction "PF5_15") (pintype "bidirectional"))
    )
    (net (code "224") (name "unconnected-(U16-PF6-Pad18)") (class "Default")
      (node (ref "U16") (pin "18") (pinfunction "PF6_18") (pintype "bidirectional"))
    )
    (net (code "225") (name "unconnected-(U16-PF12-Pad50)") (class "Default")
      (node (ref "U16") (pin "50") (pinfunction "PF12_50") (pintype "bidirectional"))
    )
    (net (code "226") (name "unconnected-(U16-PF13-Pad53)") (class "Default")
      (node (ref "U16") (pin "53") (pinfunction "PF13_53") (pintype "bidirectional"))
    )
    (net (code "227") (name "unconnected-(U16-PF14-Pad54)") (class "Default")
      (node (ref "U16") (pin "54") (pinfunction "PF14_54") (pintype "bidirectional"))
    )
    (net (code "228") (name "unconnected-(U16-PF15-Pad55)") (class "Default")
      (node (ref "U16") (pin "55") (pinfunction "PF15_55") (pintype "bidirectional"))
    )
    (net (code "229") (name "unconnected-(U16-PG0-Pad56)") (class "Default")
      (node (ref "U16") (pin "56") (pinfunction "PG0_56") (pintype "bidirectional"))
    )
    (net (code "230") (name "unconnected-(U16-PG1-Pad57)") (class "Default")
      (node (ref "U16") (pin "57") (pinfunction "PG1_57") (pintype "bidirectional"))
    )
    (net (code "231") (name "unconnected-(U16-PG2-Pad87)") (class "Default")
      (node (ref "U16") (pin "87") (pinfunction "PG2_87") (pintype "bidirectional"))
    )
    (net (code "232") (name "unconnected-(U16-PG3-Pad88)") (class "Default")
      (node (ref "U16") (pin "88") (pinfunction "PG3_88") (pintype "bidirectional"))
    )
    (net (code "233") (name "unconnected-(U16-PG4-Pad89)") (class "Default")
      (node (ref "U16") (pin "89") (pinfunction "PG4_89") (pintype "bidirectional"))
    )
    (net (code "234") (name "unconnected-(U16-PG5-Pad90)") (class "Default")
      (node (ref "U16") (pin "90") (pinfunction "PG5_90") (pintype "bidirectional"))
    )
    (net (code "235") (name "unconnected-(U16-PG6-Pad91)") (class "Default")
      (node (ref "U16") (pin "91") (pinfunction "PG6_91") (pintype "bidirectional"))
    )
    (net (code "236") (name "unconnected-(U16-PG7-Pad92)") (class "Default")
      (node (ref "U16") (pin "92") (pinfunction "PG7_92") (pintype "bidirectional"))
    )
    (net (code "237") (name "unconnected-(U16-PG8-Pad93)") (class "Default")
      (node (ref "U16") (pin "93") (pinfunction "PG8_93") (pintype "bidirectional"))
    )
    (net (code "238") (name "unconnected-(U16-PG12-Pad127)") (class "Default")
      (node (ref "U16") (pin "127") (pinfunction "PG12_127") (pintype "bidirectional"))
    )
    (net (code "239") (name "unconnected-(U16-PG13-Pad128)") (class "Default")
      (node (ref "U16") (pin "128") (pinfunction "PG13_128") (pintype "bidirectional"))
    )
    (net (code "240") (name "unconnected-(U16-PG14-Pad129)") (class "Default")
      (node (ref "U16") (pin "129") (pinfunction "PG14_129") (pintype "bidirectional"))
    )
    (net (code "241") (name "unconnected-(U16-PG15-Pad132)") (class "Default")
      (node (ref "U16") (pin "132") (pinfunction "PG15_132") (pintype "bidirectional"))
    )
    (net (code "242") (name "unconnected-(U17-NC-Pad11)") (class "Default")
      (node (ref "U17") (pin "11") (pinfunction "NC_11") (pintype "bidirectional"))
    )
    (net (code "243") (name "unconnected-(U17-P0A-Pad8)") (class "Default")
      (node (ref "U17") (pin "8") (pinfunction "P0A_8") (pintype "bidirectional"))
    )
    (net (code "244") (name "unconnected-(U17-P1A-Pad7)") (class "Default")
      (node (ref "U17") (pin "7") (pinfunction "P1A_7") (pintype "bidirectional"))
    )
    (net (code "245") (name "~{CLK_4040}") (class "Default")
      (node (ref "IC4") (pin "3") (pinfunction "1Y_3") (pintype "output"))
      (node (ref "IC4") (pin "4") (pinfunction "2A_4") (pintype "input"))
      (node (ref "IC4") (pin "5") (pinfunction "2B_5") (pintype "input"))
    )
    (net (code "246") (name "~{DONE}") (class "Default")
      (node (ref "IC4") (pin "11") (pinfunction "4Y_11") (pintype "output"))
      (node (ref "IC4") (pin "2") (pinfunction "1B_2") (pintype "input"))
    )
    (net (code "247") (name "~{RST_DRIVE}") (class "Default")
      (node (ref "IC2") (pin "2") (pinfunction "Q6_2") (pintype "output"))
      (node (ref "IC4") (pin "10") (pinfunction "3B_10") (pintype "input"))
      (node (ref "IC4") (pin "12") (pinfunction "4A_12") (pintype "input"))
      (node (ref "IC4") (pin "9") (pinfunction "3A_9") (pintype "input"))
    )
  )
)
